# Sheet_1_2024-01-18.net
KiCad netlist of a schematic drawn in Altium Designer
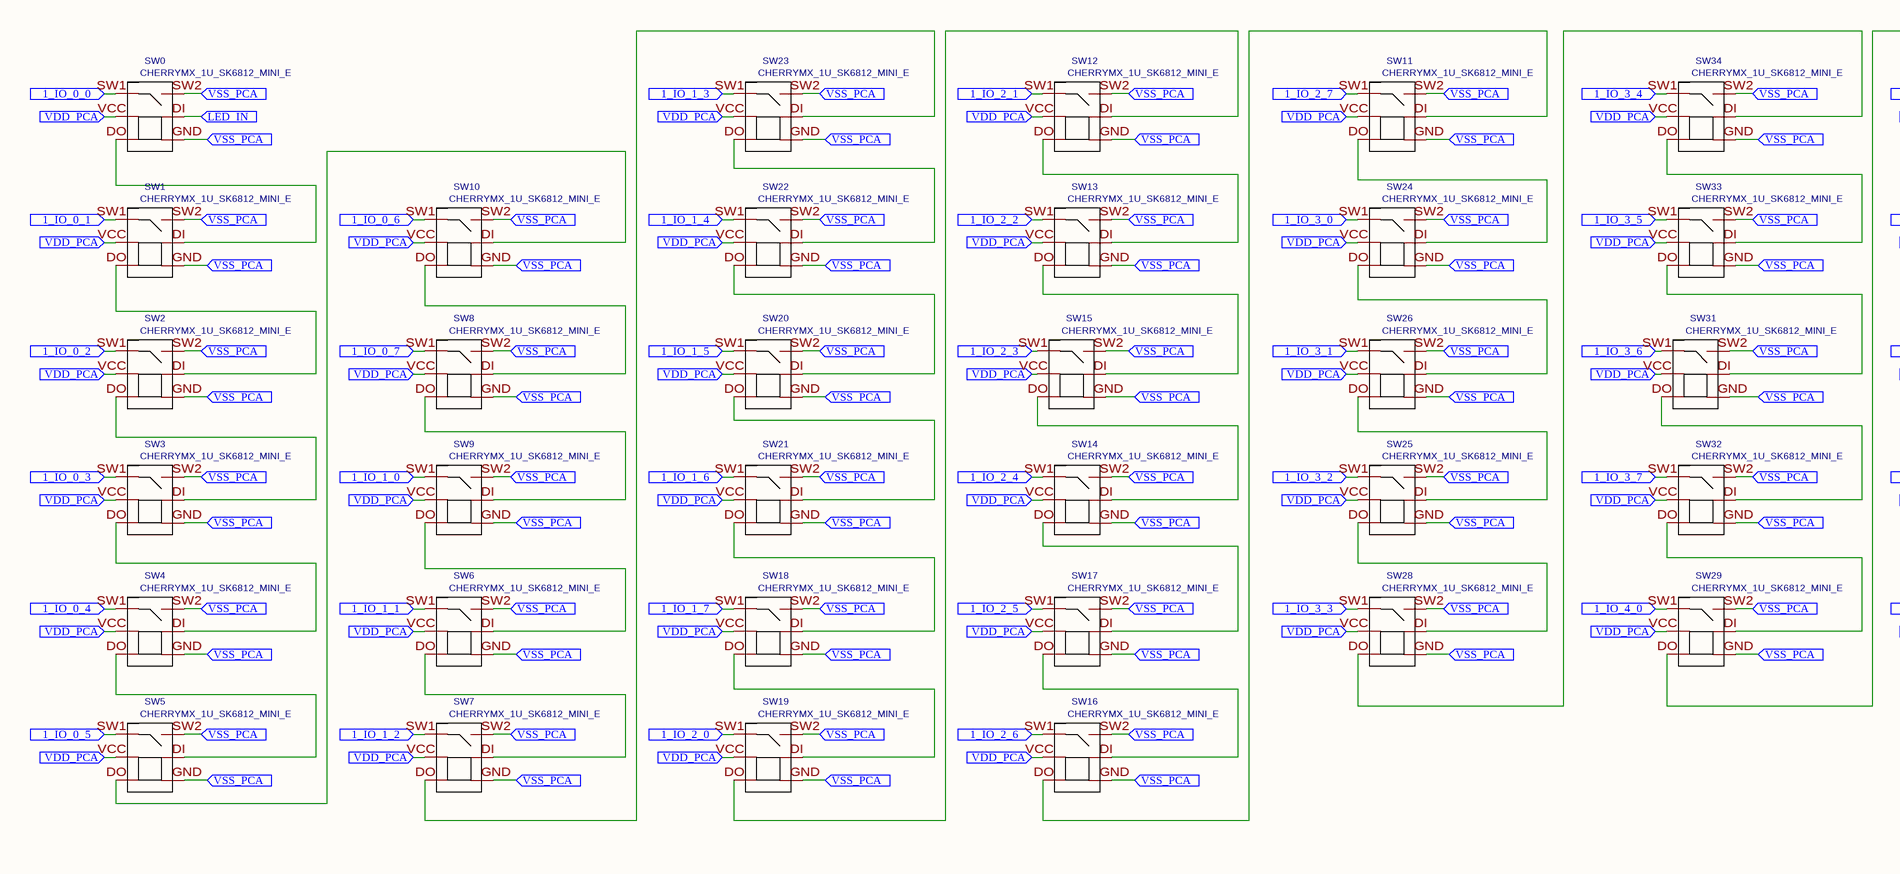
[diagram p0: Sheet_1_2024-01-18.schdoc, top left]
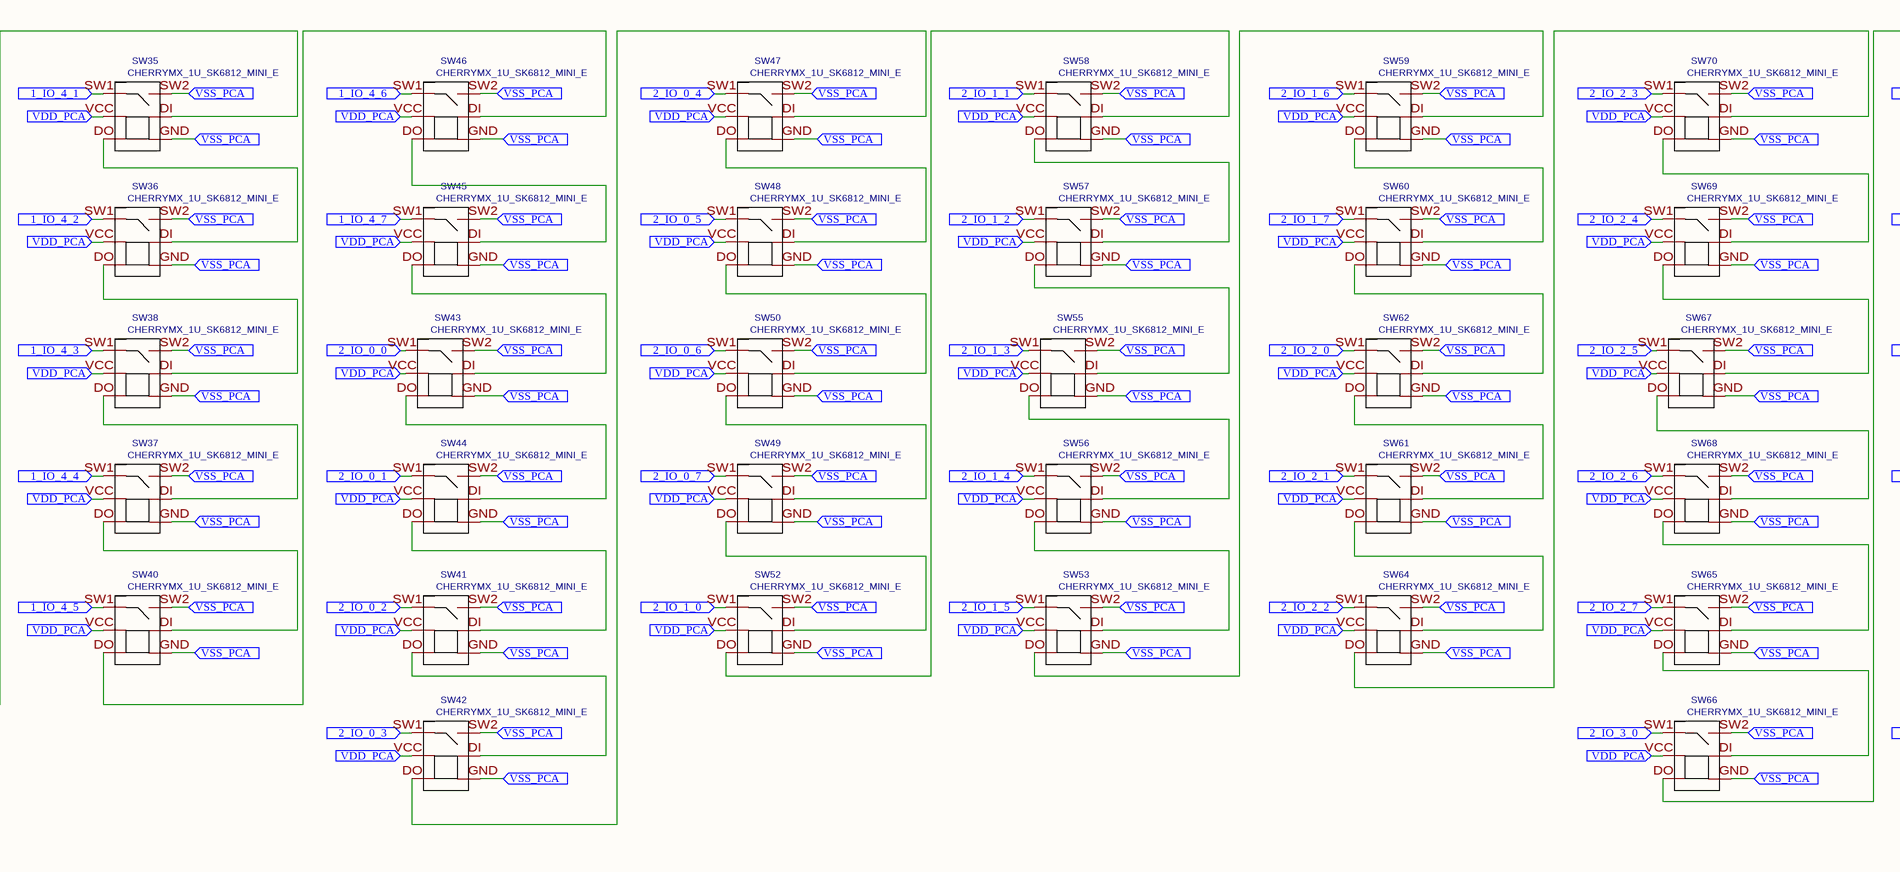
[diagram p1: Sheet_1_2024-01-18.schdoc, top middle]
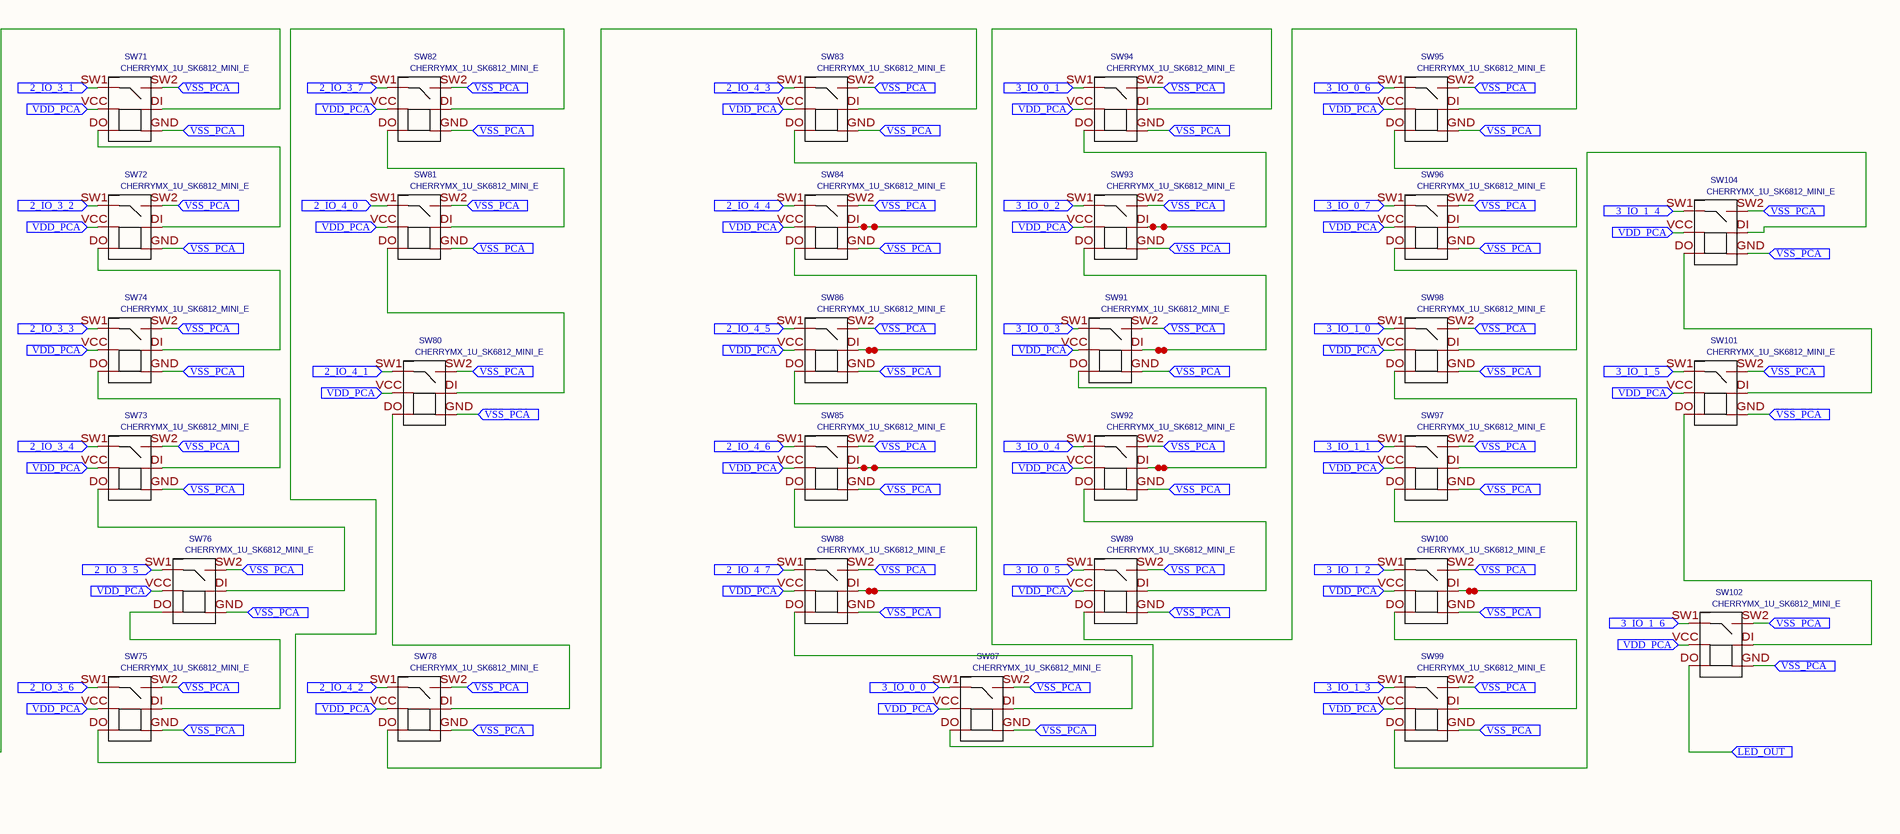
[diagram p2: Sheet_1_2024-01-18.schdoc, top right]
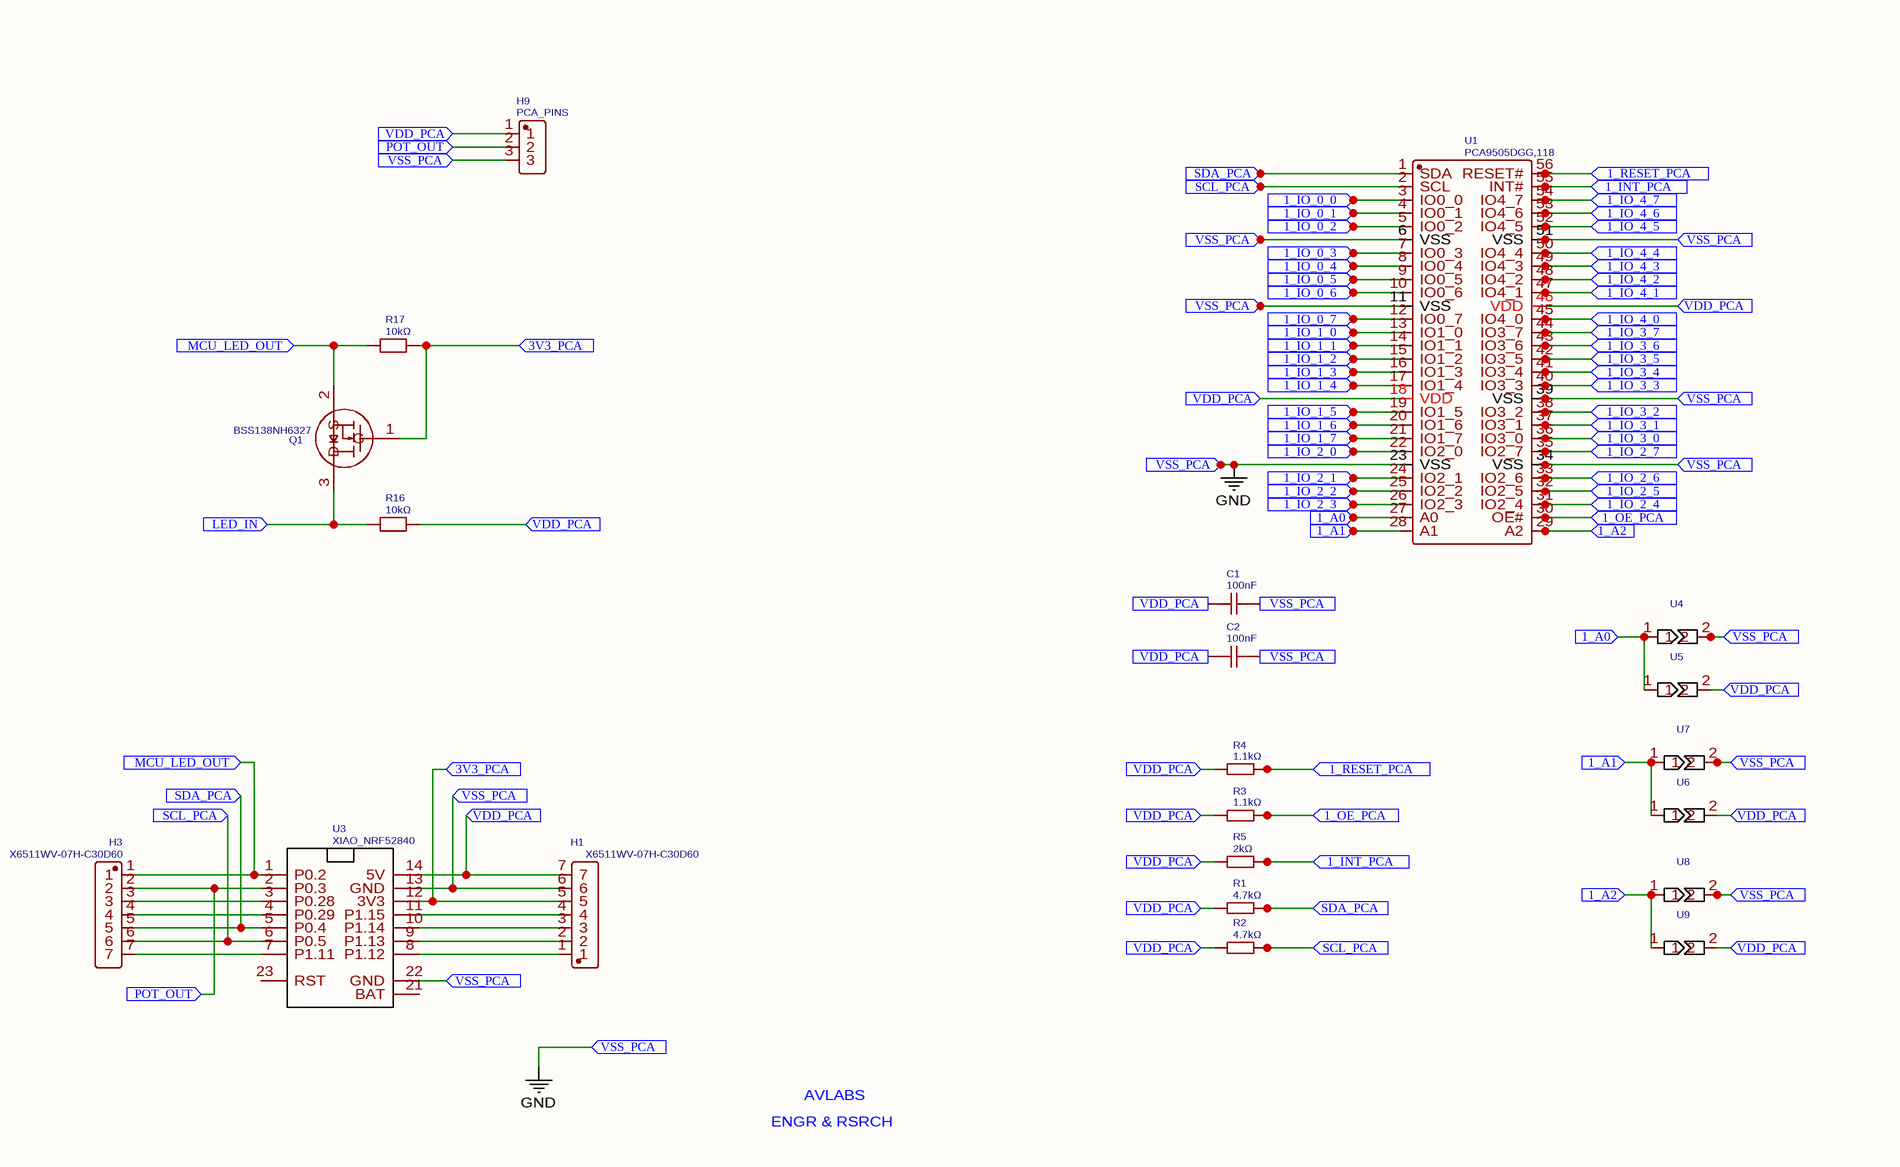
[diagram p3: Sheet_1_2024-01-18.schdoc, bottom left]
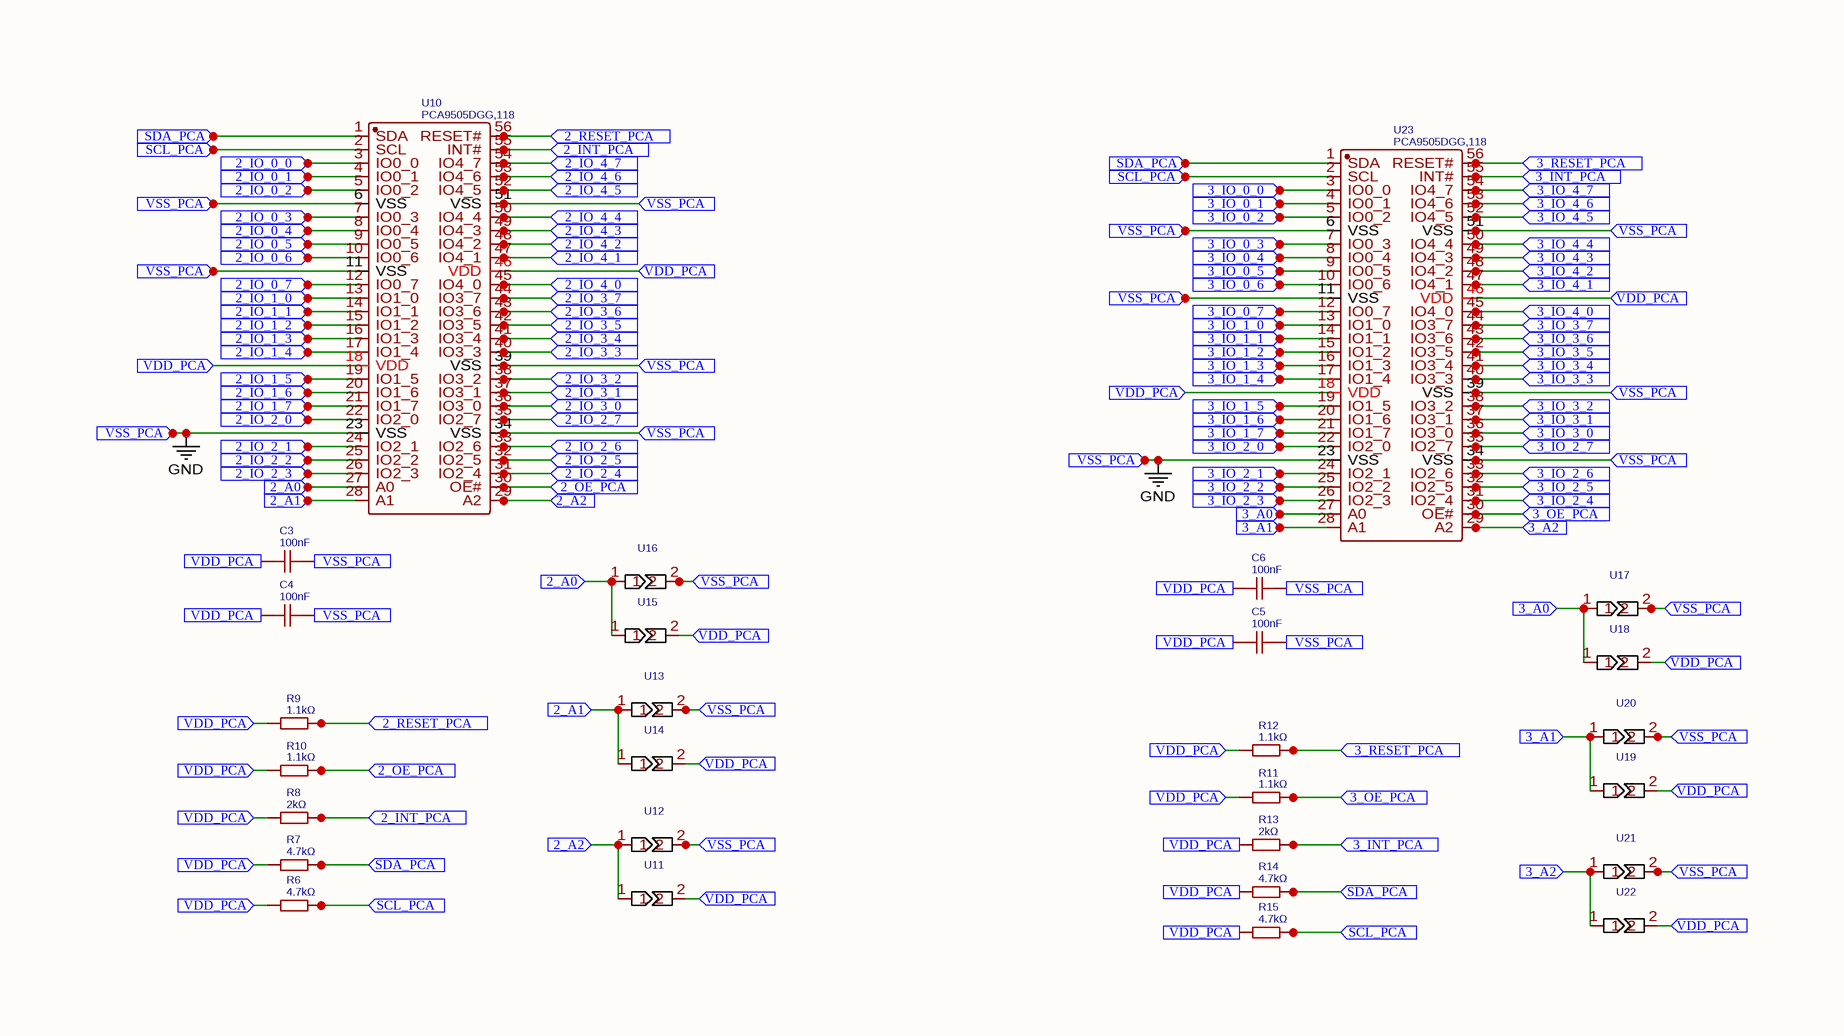
[diagram p4: Sheet_1_2024-01-18.schdoc, bottom middle]

(export (version "E")
  (design (tool "Eeschema 10.0.6"))
  (components
    (comp (ref "C1")
      (value "100nF")
      (fields
        (field (name "MANUFACTURER") "muRata(村田)")
        (field (name "MANUFACTURER PART") "GRM21BR71H104KA01L")
      )
      (libsource (lib "altium-import") (part "root_0_100nF_"))
    )
    (comp (ref "C2")
      (value "100nF")
      (fields
        (field (name "MANUFACTURER") "muRata(村田)")
        (field (name "MANUFACTURER PART") "GRM21BR71H104KA01L")
      )
      (libsource (lib "altium-import") (part "root_0_100nF_"))
    )
    (comp (ref "C3")
      (value "100nF")
      (fields
        (field (name "MANUFACTURER") "muRata(村田)")
        (field (name "MANUFACTURER PART") "GRM21BR71H104KA01L")
      )
      (libsource (lib "altium-import") (part "root_0_100nF_"))
    )
    (comp (ref "C4")
      (value "100nF")
      (fields
        (field (name "MANUFACTURER") "muRata(村田)")
        (field (name "MANUFACTURER PART") "GRM21BR71H104KA01L")
      )
      (libsource (lib "altium-import") (part "root_0_100nF_"))
    )
    (comp (ref "C5")
      (value "100nF")
      (fields
        (field (name "MANUFACTURER") "muRata(村田)")
        (field (name "MANUFACTURER PART") "GRM21BR71H104KA01L")
      )
      (libsource (lib "altium-import") (part "root_0_100nF_"))
    )
    (comp (ref "C6")
      (value "100nF")
      (fields
        (field (name "MANUFACTURER") "muRata(村田)")
        (field (name "MANUFACTURER PART") "GRM21BR71H104KA01L")
      )
      (libsource (lib "altium-import") (part "root_0_100nF_"))
    )
    (comp (ref "H1")
      (value "X6511WV-07H-C30D60")
      (fields (field (name "MANUFACTURER") "XKB Connectivity(中国星坤)") (field (name "CONTRIBUTOR") "LCSC"))
      (libsource (lib "altium-import") (part "root_2_X6511WV-07H-C30D60_"))
    )
    (comp (ref "H3")
      (value "X6511WV-07H-C30D60")
      (fields (field (name "MANUFACTURER") "XKB Connectivity(中国星坤)") (field (name "CONTRIBUTOR") "LCSC"))
      (libsource (lib "altium-import") (part "root_0_X6511WV-07H-C30D60_"))
    )
    (comp (ref "H9")
      (value "PCA_PINS")
      (fields
        (field (name "MANUFACTURER") "XKB Connectivity(中国星坤)")
        (field (name "MANUFACTURER PART") "X6511WV-03H-C30D60")
        (field (name "CONTRIBUTOR") "LCSC")
      )
      (libsource (lib "altium-import") (part "root_0_PCA_PINS_"))
    )
    (comp (ref "Q1")
      (value "BSS138NH6327")
      (fields (field (name "MANUFACTURER") "Infineon(英飞凌)") (field (name "CONTRIBUTOR") "LCSC"))
      (libsource (lib "altium-import") (part "root_0_BSS138NH6327_"))
    )
    (comp (ref "R1")
      (value "4.7kΩ")
      (fields
        (field (name "MANUFACTURER") "KOA")
        (field (name "MANUFACTURER PART") "RN732ATTD4701B25")
        (field (name "CONTRIBUTOR") "LCSC")
      )
      (libsource (lib "altium-import") (part "root_0_4.7kΩ_"))
    )
    (comp (ref "R2")
      (value "4.7kΩ")
      (fields
        (field (name "MANUFACTURER") "KOA")
        (field (name "MANUFACTURER PART") "RN732ATTD4701B25")
        (field (name "CONTRIBUTOR") "LCSC")
      )
      (libsource (lib "altium-import") (part "root_0_4.7kΩ_"))
    )
    (comp (ref "R3")
      (value "1.1kΩ")
      (fields
        (field (name "MANUFACTURER") "KOA")
        (field (name "MANUFACTURER PART") "RN732ATTD1101B25")
        (field (name "CONTRIBUTOR") "LCSC")
      )
      (libsource (lib "altium-import") (part "root_0_1.1kΩ_"))
    )
    (comp (ref "R4")
      (value "1.1kΩ")
      (fields
        (field (name "MANUFACTURER") "KOA")
        (field (name "MANUFACTURER PART") "RN732ATTD1101B25")
        (field (name "CONTRIBUTOR") "LCSC")
      )
      (libsource (lib "altium-import") (part "root_0_1.1kΩ_"))
    )
    (comp (ref "R5")
      (value "2kΩ")
      (fields
        (field (name "MANUFACTURER") "KOA")
        (field (name "MANUFACTURER PART") "RN732ATTD2001B25")
        (field (name "CONTRIBUTOR") "LCSC")
      )
      (libsource (lib "altium-import") (part "root_0_2kΩ_"))
    )
    (comp (ref "R6")
      (value "4.7kΩ")
      (fields
        (field (name "MANUFACTURER") "KOA")
        (field (name "MANUFACTURER PART") "RN732ATTD4701B25")
        (field (name "CONTRIBUTOR") "LCSC")
      )
      (libsource (lib "altium-import") (part "root_0_4.7kΩ_"))
    )
    (comp (ref "R7")
      (value "4.7kΩ")
      (fields
        (field (name "MANUFACTURER") "KOA")
        (field (name "MANUFACTURER PART") "RN732ATTD4701B25")
        (field (name "CONTRIBUTOR") "LCSC")
      )
      (libsource (lib "altium-import") (part "root_0_4.7kΩ_"))
    )
    (comp (ref "R8")
      (value "2kΩ")
      (fields
        (field (name "MANUFACTURER") "KOA")
        (field (name "MANUFACTURER PART") "RN732ATTD2001B25")
        (field (name "CONTRIBUTOR") "LCSC")
      )
      (libsource (lib "altium-import") (part "root_0_2kΩ_"))
    )
    (comp (ref "R9")
      (value "1.1kΩ")
      (fields
        (field (name "MANUFACTURER") "KOA")
        (field (name "MANUFACTURER PART") "RN732ATTD1101B25")
        (field (name "CONTRIBUTOR") "LCSC")
      )
      (libsource (lib "altium-import") (part "root_0_1.1kΩ_"))
    )
    (comp (ref "R10")
      (value "1.1kΩ")
      (fields
        (field (name "MANUFACTURER") "KOA")
        (field (name "MANUFACTURER PART") "RN732ATTD1101B25")
        (field (name "CONTRIBUTOR") "LCSC")
      )
      (libsource (lib "altium-import") (part "root_0_1.1kΩ_"))
    )
    (comp (ref "R11")
      (value "1.1kΩ")
      (fields
        (field (name "MANUFACTURER") "KOA")
        (field (name "MANUFACTURER PART") "RN732ATTD1101B25")
        (field (name "CONTRIBUTOR") "LCSC")
      )
      (libsource (lib "altium-import") (part "root_0_1.1kΩ_"))
    )
    (comp (ref "R12")
      (value "1.1kΩ")
      (fields
        (field (name "MANUFACTURER") "KOA")
        (field (name "MANUFACTURER PART") "RN732ATTD1101B25")
        (field (name "CONTRIBUTOR") "LCSC")
      )
      (libsource (lib "altium-import") (part "root_0_1.1kΩ_"))
    )
    (comp (ref "R13")
      (value "2kΩ")
      (fields
        (field (name "MANUFACTURER") "KOA")
        (field (name "MANUFACTURER PART") "RN732ATTD2001B25")
        (field (name "CONTRIBUTOR") "LCSC")
      )
      (libsource (lib "altium-import") (part "root_0_2kΩ_"))
    )
    (comp (ref "R14")
      (value "4.7kΩ")
      (fields
        (field (name "MANUFACTURER") "KOA")
        (field (name "MANUFACTURER PART") "RN732ATTD4701B25")
        (field (name "CONTRIBUTOR") "LCSC")
      )
      (libsource (lib "altium-import") (part "root_0_4.7kΩ_"))
    )
    (comp (ref "R15")
      (value "4.7kΩ")
      (fields
        (field (name "MANUFACTURER") "KOA")
        (field (name "MANUFACTURER PART") "RN732ATTD4701B25")
        (field (name "CONTRIBUTOR") "LCSC")
      )
      (libsource (lib "altium-import") (part "root_0_4.7kΩ_"))
    )
    (comp (ref "R16")
      (value "10kΩ")
      (fields
        (field (name "MANUFACTURER") "KOA")
        (field (name "MANUFACTURER PART") "RN732ATTD1002B10")
        (field (name "CONTRIBUTOR") "LCSC")
      )
      (libsource (lib "altium-import") (part "root_0_10kΩ_"))
    )
    (comp (ref "R17")
      (value "10kΩ")
      (fields
        (field (name "MANUFACTURER") "KOA")
        (field (name "MANUFACTURER PART") "RN732ATTD1002B10")
        (field (name "CONTRIBUTOR") "LCSC")
      )
      (libsource (lib "altium-import") (part "root_0_10kΩ_"))
    )
    (comp (ref "SW0")
      (value "CHERRYMX_1U_SK6812_MINI_E")
      (fields (field (name "CONTRIBUTOR") "Andrea Peron"))
      (libsource (lib "altium-import") (part "root_0_CHERRYMX_1U_SK6812_MINI_E_"))
    )
    (comp (ref "SW1")
      (value "CHERRYMX_1U_SK6812_MINI_E")
      (fields (field (name "CONTRIBUTOR") "Andrea Peron"))
      (libsource (lib "altium-import") (part "root_0_CHERRYMX_1U_SK6812_MINI_E_"))
    )
    (comp (ref "SW2")
      (value "CHERRYMX_1U_SK6812_MINI_E")
      (fields (field (name "CONTRIBUTOR") "Andrea Peron"))
      (libsource (lib "altium-import") (part "root_0_CHERRYMX_1U_SK6812_MINI_E_"))
    )
    (comp (ref "SW3")
      (value "CHERRYMX_1U_SK6812_MINI_E")
      (fields (field (name "CONTRIBUTOR") "Andrea Peron"))
      (libsource (lib "altium-import") (part "root_0_CHERRYMX_1U_SK6812_MINI_E_"))
    )
    (comp (ref "SW4")
      (value "CHERRYMX_1U_SK6812_MINI_E")
      (fields (field (name "CONTRIBUTOR") "Andrea Peron"))
      (libsource (lib "altium-import") (part "root_0_CHERRYMX_1U_SK6812_MINI_E_"))
    )
    (comp (ref "SW5")
      (value "CHERRYMX_1U_SK6812_MINI_E")
      (fields (field (name "CONTRIBUTOR") "Andrea Peron"))
      (libsource (lib "altium-import") (part "root_0_CHERRYMX_1U_SK6812_MINI_E_"))
    )
    (comp (ref "SW6")
      (value "CHERRYMX_1U_SK6812_MINI_E")
      (fields (field (name "CONTRIBUTOR") "Andrea Peron"))
      (libsource (lib "altium-import") (part "root_0_CHERRYMX_1U_SK6812_MINI_E_"))
    )
    (comp (ref "SW7")
      (value "CHERRYMX_1U_SK6812_MINI_E")
      (fields (field (name "CONTRIBUTOR") "Andrea Peron"))
      (libsource (lib "altium-import") (part "root_0_CHERRYMX_1U_SK6812_MINI_E_"))
    )
    (comp (ref "SW8")
      (value "CHERRYMX_1U_SK6812_MINI_E")
      (fields (field (name "CONTRIBUTOR") "Andrea Peron"))
      (libsource (lib "altium-import") (part "root_0_CHERRYMX_1U_SK6812_MINI_E_"))
    )
    (comp (ref "SW9")
      (value "CHERRYMX_1U_SK6812_MINI_E")
      (fields (field (name "CONTRIBUTOR") "Andrea Peron"))
      (libsource (lib "altium-import") (part "root_0_CHERRYMX_1U_SK6812_MINI_E_"))
    )
    (comp (ref "SW10")
      (value "CHERRYMX_1U_SK6812_MINI_E")
      (fields (field (name "CONTRIBUTOR") "Andrea Peron"))
      (libsource (lib "altium-import") (part "root_0_CHERRYMX_1U_SK6812_MINI_E_"))
    )
    (comp (ref "SW11")
      (value "CHERRYMX_1U_SK6812_MINI_E")
      (fields (field (name "CONTRIBUTOR") "Andrea Peron"))
      (libsource (lib "altium-import") (part "root_0_CHERRYMX_1U_SK6812_MINI_E_"))
    )
    (comp (ref "SW12")
      (value "CHERRYMX_1U_SK6812_MINI_E")
      (fields (field (name "CONTRIBUTOR") "Andrea Peron"))
      (libsource (lib "altium-import") (part "root_0_CHERRYMX_1U_SK6812_MINI_E_"))
    )
    (comp (ref "SW13")
      (value "CHERRYMX_1U_SK6812_MINI_E")
      (fields (field (name "CONTRIBUTOR") "Andrea Peron"))
      (libsource (lib "altium-import") (part "root_0_CHERRYMX_1U_SK6812_MINI_E_"))
    )
    (comp (ref "SW14")
      (value "CHERRYMX_1U_SK6812_MINI_E")
      (fields (field (name "CONTRIBUTOR") "Andrea Peron"))
      (libsource (lib "altium-import") (part "root_0_CHERRYMX_1U_SK6812_MINI_E_"))
    )
    (comp (ref "SW15")
      (value "CHERRYMX_1U_SK6812_MINI_E")
      (fields (field (name "CONTRIBUTOR") "Andrea Peron"))
      (libsource (lib "altium-import") (part "root_0_CHERRYMX_1U_SK6812_MINI_E_"))
    )
    (comp (ref "SW16")
      (value "CHERRYMX_1U_SK6812_MINI_E")
      (fields (field (name "CONTRIBUTOR") "Andrea Peron"))
      (libsource (lib "altium-import") (part "root_0_CHERRYMX_1U_SK6812_MINI_E_"))
    )
    (comp (ref "SW17")
      (value "CHERRYMX_1U_SK6812_MINI_E")
      (fields (field (name "CONTRIBUTOR") "Andrea Peron"))
      (libsource (lib "altium-import") (part "root_0_CHERRYMX_1U_SK6812_MINI_E_"))
    )
    (comp (ref "SW18")
      (value "CHERRYMX_1U_SK6812_MINI_E")
      (fields (field (name "CONTRIBUTOR") "Andrea Peron"))
      (libsource (lib "altium-import") (part "root_0_CHERRYMX_1U_SK6812_MINI_E_"))
    )
    (comp (ref "SW19")
      (value "CHERRYMX_1U_SK6812_MINI_E")
      (fields (field (name "CONTRIBUTOR") "Andrea Peron"))
      (libsource (lib "altium-import") (part "root_0_CHERRYMX_1U_SK6812_MINI_E_"))
    )
    (comp (ref "SW20")
      (value "CHERRYMX_1U_SK6812_MINI_E")
      (fields (field (name "CONTRIBUTOR") "Andrea Peron"))
      (libsource (lib "altium-import") (part "root_0_CHERRYMX_1U_SK6812_MINI_E_"))
    )
    (comp (ref "SW21")
      (value "CHERRYMX_1U_SK6812_MINI_E")
      (fields (field (name "CONTRIBUTOR") "Andrea Peron"))
      (libsource (lib "altium-import") (part "root_0_CHERRYMX_1U_SK6812_MINI_E_"))
    )
    (comp (ref "SW22")
      (value "CHERRYMX_1U_SK6812_MINI_E")
      (fields (field (name "CONTRIBUTOR") "Andrea Peron"))
      (libsource (lib "altium-import") (part "root_0_CHERRYMX_1U_SK6812_MINI_E_"))
    )
    (comp (ref "SW23")
      (value "CHERRYMX_1U_SK6812_MINI_E")
      (fields (field (name "CONTRIBUTOR") "Andrea Peron"))
      (libsource (lib "altium-import") (part "root_0_CHERRYMX_1U_SK6812_MINI_E_"))
    )
    (comp (ref "SW24")
      (value "CHERRYMX_1U_SK6812_MINI_E")
      (fields (field (name "CONTRIBUTOR") "Andrea Peron"))
      (libsource (lib "altium-import") (part "root_0_CHERRYMX_1U_SK6812_MINI_E_"))
    )
    (comp (ref "SW25")
      (value "CHERRYMX_1U_SK6812_MINI_E")
      (fields (field (name "CONTRIBUTOR") "Andrea Peron"))
      (libsource (lib "altium-import") (part "root_0_CHERRYMX_1U_SK6812_MINI_E_"))
    )
    (comp (ref "SW26")
      (value "CHERRYMX_1U_SK6812_MINI_E")
      (fields (field (name "CONTRIBUTOR") "Andrea Peron"))
      (libsource (lib "altium-import") (part "root_0_CHERRYMX_1U_SK6812_MINI_E_"))
    )
    (comp (ref "SW28")
      (value "CHERRYMX_1U_SK6812_MINI_E")
      (fields (field (name "CONTRIBUTOR") "Andrea Peron"))
      (libsource (lib "altium-import") (part "root_0_CHERRYMX_1U_SK6812_MINI_E_"))
    )
    (comp (ref "SW29")
      (value "CHERRYMX_1U_SK6812_MINI_E")
      (fields (field (name "CONTRIBUTOR") "Andrea Peron"))
      (libsource (lib "altium-import") (part "root_0_CHERRYMX_1U_SK6812_MINI_E_"))
    )
    (comp (ref "SW31")
      (value "CHERRYMX_1U_SK6812_MINI_E")
      (fields (field (name "CONTRIBUTOR") "Andrea Peron"))
      (libsource (lib "altium-import") (part "root_0_CHERRYMX_1U_SK6812_MINI_E_"))
    )
    (comp (ref "SW32")
      (value "CHERRYMX_1U_SK6812_MINI_E")
      (fields (field (name "CONTRIBUTOR") "Andrea Peron"))
      (libsource (lib "altium-import") (part "root_0_CHERRYMX_1U_SK6812_MINI_E_"))
    )
    (comp (ref "SW33")
      (value "CHERRYMX_1U_SK6812_MINI_E")
      (fields (field (name "CONTRIBUTOR") "Andrea Peron"))
      (libsource (lib "altium-import") (part "root_0_CHERRYMX_1U_SK6812_MINI_E_"))
    )
    (comp (ref "SW34")
      (value "CHERRYMX_1U_SK6812_MINI_E")
      (fields (field (name "CONTRIBUTOR") "Andrea Peron"))
      (libsource (lib "altium-import") (part "root_0_CHERRYMX_1U_SK6812_MINI_E_"))
    )
    (comp (ref "SW35")
      (value "CHERRYMX_1U_SK6812_MINI_E")
      (fields (field (name "CONTRIBUTOR") "Andrea Peron"))
      (libsource (lib "altium-import") (part "root_0_CHERRYMX_1U_SK6812_MINI_E_"))
    )
    (comp (ref "SW36")
      (value "CHERRYMX_1U_SK6812_MINI_E")
      (fields (field (name "CONTRIBUTOR") "Andrea Peron"))
      (libsource (lib "altium-import") (part "root_0_CHERRYMX_1U_SK6812_MINI_E_"))
    )
    (comp (ref "SW37")
      (value "CHERRYMX_1U_SK6812_MINI_E")
      (fields (field (name "CONTRIBUTOR") "Andrea Peron"))
      (libsource (lib "altium-import") (part "root_0_CHERRYMX_1U_SK6812_MINI_E_"))
    )
    (comp (ref "SW38")
      (value "CHERRYMX_1U_SK6812_MINI_E")
      (fields (field (name "CONTRIBUTOR") "Andrea Peron"))
      (libsource (lib "altium-import") (part "root_0_CHERRYMX_1U_SK6812_MINI_E_"))
    )
    (comp (ref "SW40")
      (value "CHERRYMX_1U_SK6812_MINI_E")
      (fields (field (name "CONTRIBUTOR") "Andrea Peron"))
      (libsource (lib "altium-import") (part "root_0_CHERRYMX_1U_SK6812_MINI_E_"))
    )
    (comp (ref "SW41")
      (value "CHERRYMX_1U_SK6812_MINI_E")
      (fields (field (name "CONTRIBUTOR") "Andrea Peron"))
      (libsource (lib "altium-import") (part "root_0_CHERRYMX_1U_SK6812_MINI_E_"))
    )
    (comp (ref "SW42")
      (value "CHERRYMX_1U_SK6812_MINI_E")
      (fields (field (name "CONTRIBUTOR") "Andrea Peron"))
      (libsource (lib "altium-import") (part "root_0_CHERRYMX_1U_SK6812_MINI_E_"))
    )
    (comp (ref "SW43")
      (value "CHERRYMX_1U_SK6812_MINI_E")
      (fields (field (name "CONTRIBUTOR") "Andrea Peron"))
      (libsource (lib "altium-import") (part "root_0_CHERRYMX_1U_SK6812_MINI_E_"))
    )
    (comp (ref "SW44")
      (value "CHERRYMX_1U_SK6812_MINI_E")
      (fields (field (name "CONTRIBUTOR") "Andrea Peron"))
      (libsource (lib "altium-import") (part "root_0_CHERRYMX_1U_SK6812_MINI_E_"))
    )
    (comp (ref "SW45")
      (value "CHERRYMX_1U_SK6812_MINI_E")
      (fields (field (name "CONTRIBUTOR") "Andrea Peron"))
      (libsource (lib "altium-import") (part "root_0_CHERRYMX_1U_SK6812_MINI_E_"))
    )
    (comp (ref "SW46")
      (value "CHERRYMX_1U_SK6812_MINI_E")
      (fields (field (name "CONTRIBUTOR") "Andrea Peron"))
      (libsource (lib "altium-import") (part "root_0_CHERRYMX_1U_SK6812_MINI_E_"))
    )
    (comp (ref "SW47")
      (value "CHERRYMX_1U_SK6812_MINI_E")
      (fields (field (name "CONTRIBUTOR") "Andrea Peron"))
      (libsource (lib "altium-import") (part "root_0_CHERRYMX_1U_SK6812_MINI_E_"))
    )
    (comp (ref "SW48")
      (value "CHERRYMX_1U_SK6812_MINI_E")
      (fields (field (name "CONTRIBUTOR") "Andrea Peron"))
      (libsource (lib "altium-import") (part "root_0_CHERRYMX_1U_SK6812_MINI_E_"))
    )
    (comp (ref "SW49")
      (value "CHERRYMX_1U_SK6812_MINI_E")
      (fields (field (name "CONTRIBUTOR") "Andrea Peron"))
      (libsource (lib "altium-import") (part "root_0_CHERRYMX_1U_SK6812_MINI_E_"))
    )
    (comp (ref "SW50")
      (value "CHERRYMX_1U_SK6812_MINI_E")
      (fields (field (name "CONTRIBUTOR") "Andrea Peron"))
      (libsource (lib "altium-import") (part "root_0_CHERRYMX_1U_SK6812_MINI_E_"))
    )
    (comp (ref "SW52")
      (value "CHERRYMX_1U_SK6812_MINI_E")
      (fields (field (name "CONTRIBUTOR") "Andrea Peron"))
      (libsource (lib "altium-import") (part "root_0_CHERRYMX_1U_SK6812_MINI_E_"))
    )
    (comp (ref "SW53")
      (value "CHERRYMX_1U_SK6812_MINI_E")
      (fields (field (name "CONTRIBUTOR") "Andrea Peron"))
      (libsource (lib "altium-import") (part "root_0_CHERRYMX_1U_SK6812_MINI_E_"))
    )
    (comp (ref "SW55")
      (value "CHERRYMX_1U_SK6812_MINI_E")
      (fields (field (name "CONTRIBUTOR") "Andrea Peron"))
      (libsource (lib "altium-import") (part "root_0_CHERRYMX_1U_SK6812_MINI_E_"))
    )
    (comp (ref "SW56")
      (value "CHERRYMX_1U_SK6812_MINI_E")
      (fields (field (name "CONTRIBUTOR") "Andrea Peron"))
      (libsource (lib "altium-import") (part "root_0_CHERRYMX_1U_SK6812_MINI_E_"))
    )
    (comp (ref "SW57")
      (value "CHERRYMX_1U_SK6812_MINI_E")
      (fields (field (name "CONTRIBUTOR") "Andrea Peron"))
      (libsource (lib "altium-import") (part "root_0_CHERRYMX_1U_SK6812_MINI_E_"))
    )
    (comp (ref "SW58")
      (value "CHERRYMX_1U_SK6812_MINI_E")
      (fields (field (name "CONTRIBUTOR") "Andrea Peron"))
      (libsource (lib "altium-import") (part "root_0_CHERRYMX_1U_SK6812_MINI_E_"))
    )
    (comp (ref "SW59")
      (value "CHERRYMX_1U_SK6812_MINI_E")
      (fields (field (name "CONTRIBUTOR") "Andrea Peron"))
      (libsource (lib "altium-import") (part "root_0_CHERRYMX_1U_SK6812_MINI_E_"))
    )
    (comp (ref "SW60")
      (value "CHERRYMX_1U_SK6812_MINI_E")
      (fields (field (name "CONTRIBUTOR") "Andrea Peron"))
      (libsource (lib "altium-import") (part "root_0_CHERRYMX_1U_SK6812_MINI_E_"))
    )
    (comp (ref "SW61")
      (value "CHERRYMX_1U_SK6812_MINI_E")
      (fields (field (name "CONTRIBUTOR") "Andrea Peron"))
      (libsource (lib "altium-import") (part "root_0_CHERRYMX_1U_SK6812_MINI_E_"))
    )
    (comp (ref "SW62")
      (value "CHERRYMX_1U_SK6812_MINI_E")
      (fields (field (name "CONTRIBUTOR") "Andrea Peron"))
      (libsource (lib "altium-import") (part "root_0_CHERRYMX_1U_SK6812_MINI_E_"))
    )
    (comp (ref "SW64")
      (value "CHERRYMX_1U_SK6812_MINI_E")
      (fields (field (name "CONTRIBUTOR") "Andrea Peron"))
      (libsource (lib "altium-import") (part "root_0_CHERRYMX_1U_SK6812_MINI_E_"))
    )
    (comp (ref "SW65")
      (value "CHERRYMX_1U_SK6812_MINI_E")
      (fields (field (name "CONTRIBUTOR") "Andrea Peron"))
      (libsource (lib "altium-import") (part "root_0_CHERRYMX_1U_SK6812_MINI_E_"))
    )
    (comp (ref "SW66")
      (value "CHERRYMX_1U_SK6812_MINI_E")
      (fields (field (name "CONTRIBUTOR") "Andrea Peron"))
      (libsource (lib "altium-import") (part "root_0_CHERRYMX_1U_SK6812_MINI_E_"))
    )
    (comp (ref "SW67")
      (value "CHERRYMX_1U_SK6812_MINI_E")
      (fields (field (name "CONTRIBUTOR") "Andrea Peron"))
      (libsource (lib "altium-import") (part "root_0_CHERRYMX_1U_SK6812_MINI_E_"))
    )
    (comp (ref "SW68")
      (value "CHERRYMX_1U_SK6812_MINI_E")
      (fields (field (name "CONTRIBUTOR") "Andrea Peron"))
      (libsource (lib "altium-import") (part "root_0_CHERRYMX_1U_SK6812_MINI_E_"))
    )
    (comp (ref "SW69")
      (value "CHERRYMX_1U_SK6812_MINI_E")
      (fields (field (name "CONTRIBUTOR") "Andrea Peron"))
      (libsource (lib "altium-import") (part "root_0_CHERRYMX_1U_SK6812_MINI_E_"))
    )
    (comp (ref "SW70")
      (value "CHERRYMX_1U_SK6812_MINI_E")
      (fields (field (name "CONTRIBUTOR") "Andrea Peron"))
      (libsource (lib "altium-import") (part "root_0_CHERRYMX_1U_SK6812_MINI_E_"))
    )
    (comp (ref "SW71")
      (value "CHERRYMX_1U_SK6812_MINI_E")
      (fields (field (name "CONTRIBUTOR") "Andrea Peron"))
      (libsource (lib "altium-import") (part "root_0_CHERRYMX_1U_SK6812_MINI_E_"))
    )
    (comp (ref "SW72")
      (value "CHERRYMX_1U_SK6812_MINI_E")
      (fields (field (name "CONTRIBUTOR") "Andrea Peron"))
      (libsource (lib "altium-import") (part "root_0_CHERRYMX_1U_SK6812_MINI_E_"))
    )
    (comp (ref "SW73")
      (value "CHERRYMX_1U_SK6812_MINI_E")
      (fields (field (name "CONTRIBUTOR") "Andrea Peron"))
      (libsource (lib "altium-import") (part "root_0_CHERRYMX_1U_SK6812_MINI_E_"))
    )
    (comp (ref "SW74")
      (value "CHERRYMX_1U_SK6812_MINI_E")
      (fields (field (name "CONTRIBUTOR") "Andrea Peron"))
      (libsource (lib "altium-import") (part "root_0_CHERRYMX_1U_SK6812_MINI_E_"))
    )
    (comp (ref "SW75")
      (value "CHERRYMX_1U_SK6812_MINI_E")
      (fields (field (name "CONTRIBUTOR") "Andrea Peron"))
      (libsource (lib "altium-import") (part "root_0_CHERRYMX_1U_SK6812_MINI_E_"))
    )
    (comp (ref "SW76")
      (value "CHERRYMX_1U_SK6812_MINI_E")
      (fields (field (name "CONTRIBUTOR") "Andrea Peron"))
      (libsource (lib "altium-import") (part "root_0_CHERRYMX_1U_SK6812_MINI_E_"))
    )
    (comp (ref "SW78")
      (value "CHERRYMX_1U_SK6812_MINI_E")
      (fields (field (name "CONTRIBUTOR") "Andrea Peron"))
      (libsource (lib "altium-import") (part "root_0_CHERRYMX_1U_SK6812_MINI_E_"))
    )
    (comp (ref "SW80")
      (value "CHERRYMX_1U_SK6812_MINI_E")
      (fields (field (name "CONTRIBUTOR") "Andrea Peron"))
      (libsource (lib "altium-import") (part "root_0_CHERRYMX_1U_SK6812_MINI_E_"))
    )
    (comp (ref "SW81")
      (value "CHERRYMX_1U_SK6812_MINI_E")
      (fields (field (name "CONTRIBUTOR") "Andrea Peron"))
      (libsource (lib "altium-import") (part "root_0_CHERRYMX_1U_SK6812_MINI_E_"))
    )
    (comp (ref "SW82")
      (value "CHERRYMX_1U_SK6812_MINI_E")
      (fields (field (name "CONTRIBUTOR") "Andrea Peron"))
      (libsource (lib "altium-import") (part "root_0_CHERRYMX_1U_SK6812_MINI_E_"))
    )
    (comp (ref "SW83")
      (value "CHERRYMX_1U_SK6812_MINI_E")
      (fields (field (name "CONTRIBUTOR") "Andrea Peron"))
      (libsource (lib "altium-import") (part "root_0_CHERRYMX_1U_SK6812_MINI_E_"))
    )
    (comp (ref "SW84")
      (value "CHERRYMX_1U_SK6812_MINI_E")
      (fields (field (name "CONTRIBUTOR") "Andrea Peron"))
      (libsource (lib "altium-import") (part "root_0_CHERRYMX_1U_SK6812_MINI_E_"))
    )
    (comp (ref "SW85")
      (value "CHERRYMX_1U_SK6812_MINI_E")
      (fields (field (name "CONTRIBUTOR") "Andrea Peron"))
      (libsource (lib "altium-import") (part "root_0_CHERRYMX_1U_SK6812_MINI_E_"))
    )
    (comp (ref "SW86")
      (value "CHERRYMX_1U_SK6812_MINI_E")
      (fields (field (name "CONTRIBUTOR") "Andrea Peron"))
      (libsource (lib "altium-import") (part "root_0_CHERRYMX_1U_SK6812_MINI_E_"))
    )
    (comp (ref "SW87")
      (value "CHERRYMX_1U_SK6812_MINI_E")
      (fields (field (name "CONTRIBUTOR") "Andrea Peron"))
      (libsource (lib "altium-import") (part "root_0_CHERRYMX_1U_SK6812_MINI_E_"))
    )
    (comp (ref "SW88")
      (value "CHERRYMX_1U_SK6812_MINI_E")
      (fields (field (name "CONTRIBUTOR") "Andrea Peron"))
      (libsource (lib "altium-import") (part "root_0_CHERRYMX_1U_SK6812_MINI_E_"))
    )
    (comp (ref "SW89")
      (value "CHERRYMX_1U_SK6812_MINI_E")
      (fields (field (name "CONTRIBUTOR") "Andrea Peron"))
      (libsource (lib "altium-import") (part "root_0_CHERRYMX_1U_SK6812_MINI_E_"))
    )
    (comp (ref "SW91")
      (value "CHERRYMX_1U_SK6812_MINI_E")
      (fields (field (name "CONTRIBUTOR") "Andrea Peron"))
      (libsource (lib "altium-import") (part "root_0_CHERRYMX_1U_SK6812_MINI_E_"))
    )
    (comp (ref "SW92")
      (value "CHERRYMX_1U_SK6812_MINI_E")
      (fields (field (name "CONTRIBUTOR") "Andrea Peron"))
      (libsource (lib "altium-import") (part "root_0_CHERRYMX_1U_SK6812_MINI_E_"))
    )
    (comp (ref "SW93")
      (value "CHERRYMX_1U_SK6812_MINI_E")
      (fields (field (name "CONTRIBUTOR") "Andrea Peron"))
      (libsource (lib "altium-import") (part "root_0_CHERRYMX_1U_SK6812_MINI_E_"))
    )
    (comp (ref "SW94")
      (value "CHERRYMX_1U_SK6812_MINI_E")
      (fields (field (name "CONTRIBUTOR") "Andrea Peron"))
      (libsource (lib "altium-import") (part "root_0_CHERRYMX_1U_SK6812_MINI_E_"))
    )
    (comp (ref "SW95")
      (value "CHERRYMX_1U_SK6812_MINI_E")
      (fields (field (name "CONTRIBUTOR") "Andrea Peron"))
      (libsource (lib "altium-import") (part "root_0_CHERRYMX_1U_SK6812_MINI_E_"))
    )
    (comp (ref "SW96")
      (value "CHERRYMX_1U_SK6812_MINI_E")
      (fields (field (name "CONTRIBUTOR") "Andrea Peron"))
      (libsource (lib "altium-import") (part "root_0_CHERRYMX_1U_SK6812_MINI_E_"))
    )
    (comp (ref "SW97")
      (value "CHERRYMX_1U_SK6812_MINI_E")
      (fields (field (name "CONTRIBUTOR") "Andrea Peron"))
      (libsource (lib "altium-import") (part "root_0_CHERRYMX_1U_SK6812_MINI_E_"))
    )
    (comp (ref "SW98")
      (value "CHERRYMX_1U_SK6812_MINI_E")
      (fields (field (name "CONTRIBUTOR") "Andrea Peron"))
      (libsource (lib "altium-import") (part "root_0_CHERRYMX_1U_SK6812_MINI_E_"))
    )
    (comp (ref "SW99")
      (value "CHERRYMX_1U_SK6812_MINI_E")
      (fields (field (name "CONTRIBUTOR") "Andrea Peron"))
      (libsource (lib "altium-import") (part "root_0_CHERRYMX_1U_SK6812_MINI_E_"))
    )
    (comp (ref "SW100")
      (value "CHERRYMX_1U_SK6812_MINI_E")
      (fields (field (name "CONTRIBUTOR") "Andrea Peron"))
      (libsource (lib "altium-import") (part "root_0_CHERRYMX_1U_SK6812_MINI_E_"))
    )
    (comp (ref "SW101")
      (value "CHERRYMX_1U_SK6812_MINI_E")
      (fields (field (name "CONTRIBUTOR") "Andrea Peron"))
      (libsource (lib "altium-import") (part "root_0_CHERRYMX_1U_SK6812_MINI_E_"))
    )
    (comp (ref "SW102")
      (value "CHERRYMX_1U_SK6812_MINI_E")
      (fields (field (name "CONTRIBUTOR") "Andrea Peron"))
      (libsource (lib "altium-import") (part "root_0_CHERRYMX_1U_SK6812_MINI_E_"))
    )
    (comp (ref "SW104")
      (value "CHERRYMX_1U_SK6812_MINI_E")
      (fields (field (name "CONTRIBUTOR") "Andrea Peron"))
      (libsource (lib "altium-import") (part "root_0_CHERRYMX_1U_SK6812_MINI_E_"))
    )
    (comp (ref "U1")
      (value "PCA9505DGG,118")
      (fields (field (name "MANUFACTURER") "NXP(恩智浦)") (field (name "CONTRIBUTOR") "LCSC"))
      (libsource (lib "altium-import") (part "root_0_PCA9505DGG,118_"))
    )
    (comp (ref "U3")
      (value "XIAO_NRF52840")
      (fields (field (name "CONTRIBUTOR") "Kushal Soni"))
      (libsource (lib "altium-import") (part "root_0_XIAO_NRF52840_"))
    )
    (comp (ref "U4")
      (value "beautiful-solderbridge")
      (fields (field (name "CONTRIBUTOR") "loic.rochat"))
      (libsource (lib "altium-import") (part "root_0_beautiful-solderbridge_"))
    )
    (comp (ref "U5")
      (value "beautiful-solderbridge")
      (fields (field (name "CONTRIBUTOR") "loic.rochat"))
      (libsource (lib "altium-import") (part "root_0_beautiful-solderbridge_"))
    )
    (comp (ref "U6")
      (value "beautiful-solderbridge")
      (fields (field (name "CONTRIBUTOR") "loic.rochat"))
      (libsource (lib "altium-import") (part "root_0_beautiful-solderbridge_"))
    )
    (comp (ref "U7")
      (value "beautiful-solderbridge")
      (fields (field (name "CONTRIBUTOR") "loic.rochat"))
      (libsource (lib "altium-import") (part "root_0_beautiful-solderbridge_"))
    )
    (comp (ref "U8")
      (value "beautiful-solderbridge")
      (fields (field (name "CONTRIBUTOR") "loic.rochat"))
      (libsource (lib "altium-import") (part "root_0_beautiful-solderbridge_"))
    )
    (comp (ref "U9")
      (value "beautiful-solderbridge")
      (fields (field (name "CONTRIBUTOR") "loic.rochat"))
      (libsource (lib "altium-import") (part "root_0_beautiful-solderbridge_"))
    )
    (comp (ref "U10")
      (value "PCA9505DGG,118")
      (fields (field (name "MANUFACTURER") "NXP(恩智浦)") (field (name "CONTRIBUTOR") "LCSC"))
      (libsource (lib "altium-import") (part "root_0_PCA9505DGG,118_"))
    )
    (comp (ref "U11")
      (value "beautiful-solderbridge")
      (fields (field (name "CONTRIBUTOR") "loic.rochat"))
      (libsource (lib "altium-import") (part "root_0_beautiful-solderbridge_"))
    )
    (comp (ref "U12")
      (value "beautiful-solderbridge")
      (fields (field (name "CONTRIBUTOR") "loic.rochat"))
      (libsource (lib "altium-import") (part "root_0_beautiful-solderbridge_"))
    )
    (comp (ref "U13")
      (value "beautiful-solderbridge")
      (fields (field (name "CONTRIBUTOR") "loic.rochat"))
      (libsource (lib "altium-import") (part "root_0_beautiful-solderbridge_"))
    )
    (comp (ref "U14")
      (value "beautiful-solderbridge")
      (fields (field (name "CONTRIBUTOR") "loic.rochat"))
      (libsource (lib "altium-import") (part "root_0_beautiful-solderbridge_"))
    )
    (comp (ref "U15")
      (value "beautiful-solderbridge")
      (fields (field (name "CONTRIBUTOR") "loic.rochat"))
      (libsource (lib "altium-import") (part "root_0_beautiful-solderbridge_"))
    )
    (comp (ref "U16")
      (value "beautiful-solderbridge")
      (fields (field (name "CONTRIBUTOR") "loic.rochat"))
      (libsource (lib "altium-import") (part "root_0_beautiful-solderbridge_"))
    )
    (comp (ref "U17")
      (value "beautiful-solderbridge")
      (fields (field (name "CONTRIBUTOR") "loic.rochat"))
      (libsource (lib "altium-import") (part "root_0_beautiful-solderbridge_"))
    )
    (comp (ref "U18")
      (value "beautiful-solderbridge")
      (fields (field (name "CONTRIBUTOR") "loic.rochat"))
      (libsource (lib "altium-import") (part "root_0_beautiful-solderbridge_"))
    )
    (comp (ref "U19")
      (value "beautiful-solderbridge")
      (fields (field (name "CONTRIBUTOR") "loic.rochat"))
      (libsource (lib "altium-import") (part "root_0_beautiful-solderbridge_"))
    )
    (comp (ref "U20")
      (value "beautiful-solderbridge")
      (fields (field (name "CONTRIBUTOR") "loic.rochat"))
      (libsource (lib "altium-import") (part "root_0_beautiful-solderbridge_"))
    )
    (comp (ref "U21")
      (value "beautiful-solderbridge")
      (fields (field (name "CONTRIBUTOR") "loic.rochat"))
      (libsource (lib "altium-import") (part "root_0_beautiful-solderbridge_"))
    )
    (comp (ref "U22")
      (value "beautiful-solderbridge")
      (fields (field (name "CONTRIBUTOR") "loic.rochat"))
      (libsource (lib "altium-import") (part "root_0_beautiful-solderbridge_"))
    )
    (comp (ref "U23")
      (value "PCA9505DGG,118")
      (fields (field (name "MANUFACTURER") "NXP(恩智浦)") (field (name "CONTRIBUTOR") "LCSC"))
      (libsource (lib "altium-import") (part "root_0_PCA9505DGG,118_"))
    )
  )
  (nets
    (net (code "1") (name "/1_A0") (class "Default")
      (node (ref "U1") (pin "27") (pinfunction "A0_27") (pintype "passive"))
      (node (ref "U4") (pin "1") (pinfunction "1_1") (pintype "passive"))
      (node (ref "U5") (pin "1") (pinfunction "1_1") (pintype "passive"))
    )
    (net (code "2") (name "/1_A1") (class "Default")
      (node (ref "U1") (pin "28") (pinfunction "A1_28") (pintype "passive"))
      (node (ref "U6") (pin "1") (pinfunction "1_1") (pintype "passive"))
      (node (ref "U7") (pin "1") (pinfunction "1_1") (pintype "passive"))
    )
    (net (code "3") (name "/1_A2") (class "Default")
      (node (ref "U1") (pin "29") (pinfunction "A2_29") (pintype "passive"))
      (node (ref "U8") (pin "1") (pinfunction "1_1") (pintype "passive"))
      (node (ref "U9") (pin "1") (pinfunction "1_1") (pintype "passive"))
    )
    (net (code "4") (name "/1_INT_PCA") (class "Default")
      (node (ref "R5") (pin "2") (pinfunction "2_2") (pintype "passive"))
      (node (ref "U1") (pin "55") (pinfunction "INT#_55") (pintype "passive"))
    )
    (net (code "5") (name "/1_IO_0_0") (class "Default")
      (node (ref "SW0") (pin "SW1") (pinfunction "SW1_SW1") (pintype "passive"))
      (node (ref "U1") (pin "3") (pinfunction "IO0_0_3") (pintype "passive"))
    )
    (net (code "6") (name "/1_IO_0_1") (class "Default")
      (node (ref "SW1") (pin "SW1") (pinfunction "SW1_SW1") (pintype "passive"))
      (node (ref "U1") (pin "4") (pinfunction "IO0_1_4") (pintype "passive"))
    )
    (net (code "7") (name "/1_IO_0_2") (class "Default")
      (node (ref "SW2") (pin "SW1") (pinfunction "SW1_SW1") (pintype "passive"))
      (node (ref "U1") (pin "5") (pinfunction "IO0_2_5") (pintype "passive"))
    )
    (net (code "8") (name "/1_IO_0_3") (class "Default")
      (node (ref "SW3") (pin "SW1") (pinfunction "SW1_SW1") (pintype "passive"))
      (node (ref "U1") (pin "7") (pinfunction "IO0_3_7") (pintype "passive"))
    )
    (net (code "9") (name "/1_IO_0_4") (class "Default")
      (node (ref "SW4") (pin "SW1") (pinfunction "SW1_SW1") (pintype "passive"))
      (node (ref "U1") (pin "8") (pinfunction "IO0_4_8") (pintype "passive"))
    )
    (net (code "10") (name "/1_IO_0_5") (class "Default")
      (node (ref "SW5") (pin "SW1") (pinfunction "SW1_SW1") (pintype "passive"))
      (node (ref "U1") (pin "9") (pinfunction "IO0_5_9") (pintype "passive"))
    )
    (net (code "11") (name "/1_IO_0_6") (class "Default")
      (node (ref "SW10") (pin "SW1") (pinfunction "SW1_SW1") (pintype "passive"))
      (node (ref "U1") (pin "10") (pinfunction "IO0_6_10") (pintype "passive"))
    )
    (net (code "12") (name "/1_IO_0_7") (class "Default")
      (node (ref "SW8") (pin "SW1") (pinfunction "SW1_SW1") (pintype "passive"))
      (node (ref "U1") (pin "12") (pinfunction "IO0_7_12") (pintype "passive"))
    )
    (net (code "13") (name "/1_IO_1_0") (class "Default")
      (node (ref "SW9") (pin "SW1") (pinfunction "SW1_SW1") (pintype "passive"))
      (node (ref "U1") (pin "13") (pinfunction "IO1_0_13") (pintype "passive"))
    )
    (net (code "14") (name "/1_IO_1_1") (class "Default")
      (node (ref "SW6") (pin "SW1") (pinfunction "SW1_SW1") (pintype "passive"))
      (node (ref "U1") (pin "14") (pinfunction "IO1_1_14") (pintype "passive"))
    )
    (net (code "15") (name "/1_IO_1_2") (class "Default")
      (node (ref "SW7") (pin "SW1") (pinfunction "SW1_SW1") (pintype "passive"))
      (node (ref "U1") (pin "15") (pinfunction "IO1_2_15") (pintype "passive"))
    )
    (net (code "16") (name "/1_IO_1_3") (class "Default")
      (node (ref "SW23") (pin "SW1") (pinfunction "SW1_SW1") (pintype "passive"))
      (node (ref "U1") (pin "16") (pinfunction "IO1_3_16") (pintype "passive"))
    )
    (net (code "17") (name "/1_IO_1_4") (class "Default")
      (node (ref "SW22") (pin "SW1") (pinfunction "SW1_SW1") (pintype "passive"))
      (node (ref "U1") (pin "17") (pinfunction "IO1_4_17") (pintype "passive"))
    )
    (net (code "18") (name "/1_IO_1_5") (class "Default")
      (node (ref "SW20") (pin "SW1") (pinfunction "SW1_SW1") (pintype "passive"))
      (node (ref "U1") (pin "19") (pinfunction "IO1_5_19") (pintype "passive"))
    )
    (net (code "19") (name "/1_IO_1_6") (class "Default")
      (node (ref "SW21") (pin "SW1") (pinfunction "SW1_SW1") (pintype "passive"))
      (node (ref "U1") (pin "20") (pinfunction "IO1_6_20") (pintype "passive"))
    )
    (net (code "20") (name "/1_IO_1_7") (class "Default")
      (node (ref "SW18") (pin "SW1") (pinfunction "SW1_SW1") (pintype "passive"))
      (node (ref "U1") (pin "21") (pinfunction "IO1_7_21") (pintype "passive"))
    )
    (net (code "21") (name "/1_IO_2_0") (class "Default")
      (node (ref "SW19") (pin "SW1") (pinfunction "SW1_SW1") (pintype "passive"))
      (node (ref "U1") (pin "22") (pinfunction "IO2_0_22") (pintype "passive"))
    )
    (net (code "22") (name "/1_IO_2_1") (class "Default")
      (node (ref "SW12") (pin "SW1") (pinfunction "SW1_SW1") (pintype "passive"))
      (node (ref "U1") (pin "24") (pinfunction "IO2_1_24") (pintype "passive"))
    )
    (net (code "23") (name "/1_IO_2_2") (class "Default")
      (node (ref "SW13") (pin "SW1") (pinfunction "SW1_SW1") (pintype "passive"))
      (node (ref "U1") (pin "25") (pinfunction "IO2_2_25") (pintype "passive"))
    )
    (net (code "24") (name "/1_IO_2_3") (class "Default")
      (node (ref "SW15") (pin "SW1") (pinfunction "SW1_SW1") (pintype "passive"))
      (node (ref "U1") (pin "26") (pinfunction "IO2_3_26") (pintype "passive"))
    )
    (net (code "25") (name "/1_IO_2_4") (class "Default")
      (node (ref "SW14") (pin "SW1") (pinfunction "SW1_SW1") (pintype "passive"))
      (node (ref "U1") (pin "31") (pinfunction "IO2_4_31") (pintype "passive"))
    )
    (net (code "26") (name "/1_IO_2_5") (class "Default")
      (node (ref "SW17") (pin "SW1") (pinfunction "SW1_SW1") (pintype "passive"))
      (node (ref "U1") (pin "32") (pinfunction "IO2_5_32") (pintype "passive"))
    )
    (net (code "27") (name "/1_IO_2_6") (class "Default")
      (node (ref "SW16") (pin "SW1") (pinfunction "SW1_SW1") (pintype "passive"))
      (node (ref "U1") (pin "33") (pinfunction "IO2_6_33") (pintype "passive"))
    )
    (net (code "28") (name "/1_IO_2_7") (class "Default")
      (node (ref "SW11") (pin "SW1") (pinfunction "SW1_SW1") (pintype "passive"))
      (node (ref "U1") (pin "35") (pinfunction "IO2_7_35") (pintype "passive"))
    )
    (net (code "29") (name "/1_IO_3_0") (class "Default")
      (node (ref "SW24") (pin "SW1") (pinfunction "SW1_SW1") (pintype "passive"))
      (node (ref "U1") (pin "36") (pinfunction "IO3_0_36") (pintype "passive"))
    )
    (net (code "30") (name "/1_IO_3_1") (class "Default")
      (node (ref "SW26") (pin "SW1") (pinfunction "SW1_SW1") (pintype "passive"))
      (node (ref "U1") (pin "37") (pinfunction "IO3_1_37") (pintype "passive"))
    )
    (net (code "31") (name "/1_IO_3_2") (class "Default")
      (node (ref "SW25") (pin "SW1") (pinfunction "SW1_SW1") (pintype "passive"))
      (node (ref "U1") (pin "38") (pinfunction "IO3_2_38") (pintype "passive"))
    )
    (net (code "32") (name "/1_IO_3_3") (class "Default")
      (node (ref "SW28") (pin "SW1") (pinfunction "SW1_SW1") (pintype "passive"))
      (node (ref "U1") (pin "40") (pinfunction "IO3_3_40") (pintype "passive"))
    )
    (net (code "33") (name "/1_IO_3_4") (class "Default")
      (node (ref "SW34") (pin "SW1") (pinfunction "SW1_SW1") (pintype "passive"))
      (node (ref "U1") (pin "41") (pinfunction "IO3_4_41") (pintype "passive"))
    )
    (net (code "34") (name "/1_IO_3_5") (class "Default")
      (node (ref "SW33") (pin "SW1") (pinfunction "SW1_SW1") (pintype "passive"))
      (node (ref "U1") (pin "42") (pinfunction "IO3_5_42") (pintype "passive"))
    )
    (net (code "35") (name "/1_IO_3_6") (class "Default")
      (node (ref "SW31") (pin "SW1") (pinfunction "SW1_SW1") (pintype "passive"))
      (node (ref "U1") (pin "43") (pinfunction "IO3_6_43") (pintype "passive"))
    )
    (net (code "36") (name "/1_IO_3_7") (class "Default")
      (node (ref "SW32") (pin "SW1") (pinfunction "SW1_SW1") (pintype "passive"))
      (node (ref "U1") (pin "44") (pinfunction "IO3_7_44") (pintype "passive"))
    )
    (net (code "37") (name "/1_IO_4_0") (class "Default")
      (node (ref "SW29") (pin "SW1") (pinfunction "SW1_SW1") (pintype "passive"))
      (node (ref "U1") (pin "45") (pinfunction "IO4_0_45") (pintype "passive"))
    )
    (net (code "38") (name "/1_IO_4_1") (class "Default")
      (node (ref "SW35") (pin "SW1") (pinfunction "SW1_SW1") (pintype "passive"))
      (node (ref "U1") (pin "47") (pinfunction "IO4_1_47") (pintype "passive"))
    )
    (net (code "39") (name "/1_IO_4_2") (class "Default")
      (node (ref "SW36") (pin "SW1") (pinfunction "SW1_SW1") (pintype "passive"))
      (node (ref "U1") (pin "48") (pinfunction "IO4_2_48") (pintype "passive"))
    )
    (net (code "40") (name "/1_IO_4_3") (class "Default")
      (node (ref "SW38") (pin "SW1") (pinfunction "SW1_SW1") (pintype "passive"))
      (node (ref "U1") (pin "49") (pinfunction "IO4_3_49") (pintype "passive"))
    )
    (net (code "41") (name "/1_IO_4_4") (class "Default")
      (node (ref "SW37") (pin "SW1") (pinfunction "SW1_SW1") (pintype "passive"))
      (node (ref "U1") (pin "50") (pinfunction "IO4_4_50") (pintype "passive"))
    )
    (net (code "42") (name "/1_IO_4_5") (class "Default")
      (node (ref "SW40") (pin "SW1") (pinfunction "SW1_SW1") (pintype "passive"))
      (node (ref "U1") (pin "52") (pinfunction "IO4_5_52") (pintype "passive"))
    )
    (net (code "43") (name "/1_IO_4_6") (class "Default")
      (node (ref "SW46") (pin "SW1") (pinfunction "SW1_SW1") (pintype "passive"))
      (node (ref "U1") (pin "53") (pinfunction "IO4_6_53") (pintype "passive"))
    )
    (net (code "44") (name "/1_IO_4_7") (class "Default")
      (node (ref "SW45") (pin "SW1") (pinfunction "SW1_SW1") (pintype "passive"))
      (node (ref "U1") (pin "54") (pinfunction "IO4_7_54") (pintype "passive"))
    )
    (net (code "45") (name "/1_OE_PCA") (class "Default")
      (node (ref "R3") (pin "2") (pinfunction "2_2") (pintype "passive"))
      (node (ref "U1") (pin "30") (pinfunction "OE#_30") (pintype "passive"))
    )
    (net (code "46") (name "/1_RESET_PCA") (class "Default")
      (node (ref "R4") (pin "2") (pinfunction "2_2") (pintype "passive"))
      (node (ref "U1") (pin "56") (pinfunction "RESET#_56") (pintype "passive"))
    )
    (net (code "47") (name "/2_A0") (class "Default")
      (node (ref "U10") (pin "27") (pinfunction "A0_27") (pintype "passive"))
      (node (ref "U15") (pin "1") (pinfunction "1_1") (pintype "passive"))
      (node (ref "U16") (pin "1") (pinfunction "1_1") (pintype "passive"))
    )
    (net (code "48") (name "/2_A1") (class "Default")
      (node (ref "U10") (pin "28") (pinfunction "A1_28") (pintype "passive"))
      (node (ref "U13") (pin "1") (pinfunction "1_1") (pintype "passive"))
      (node (ref "U14") (pin "1") (pinfunction "1_1") (pintype "passive"))
    )
    (net (code "49") (name "/2_A2") (class "Default")
      (node (ref "U10") (pin "29") (pinfunction "A2_29") (pintype "passive"))
      (node (ref "U11") (pin "1") (pinfunction "1_1") (pintype "passive"))
      (node (ref "U12") (pin "1") (pinfunction "1_1") (pintype "passive"))
    )
    (net (code "50") (name "/2_INT_PCA") (class "Default")
      (node (ref "R8") (pin "2") (pinfunction "2_2") (pintype "passive"))
      (node (ref "U10") (pin "55") (pinfunction "INT#_55") (pintype "passive"))
    )
    (net (code "51") (name "/2_IO_0_0") (class "Default")
      (node (ref "SW43") (pin "SW1") (pinfunction "SW1_SW1") (pintype "passive"))
      (node (ref "U10") (pin "3") (pinfunction "IO0_0_3") (pintype "passive"))
    )
    (net (code "52") (name "/2_IO_0_1") (class "Default")
      (node (ref "SW44") (pin "SW1") (pinfunction "SW1_SW1") (pintype "passive"))
      (node (ref "U10") (pin "4") (pinfunction "IO0_1_4") (pintype "passive"))
    )
    (net (code "53") (name "/2_IO_0_2") (class "Default")
      (node (ref "SW41") (pin "SW1") (pinfunction "SW1_SW1") (pintype "passive"))
      (node (ref "U10") (pin "5") (pinfunction "IO0_2_5") (pintype "passive"))
    )
    (net (code "54") (name "/2_IO_0_3") (class "Default")
      (node (ref "SW42") (pin "SW1") (pinfunction "SW1_SW1") (pintype "passive"))
      (node (ref "U10") (pin "7") (pinfunction "IO0_3_7") (pintype "passive"))
    )
    (net (code "55") (name "/2_IO_0_4") (class "Default")
      (node (ref "SW47") (pin "SW1") (pinfunction "SW1_SW1") (pintype "passive"))
      (node (ref "U10") (pin "8") (pinfunction "IO0_4_8") (pintype "passive"))
    )
    (net (code "56") (name "/2_IO_0_5") (class "Default")
      (node (ref "SW48") (pin "SW1") (pinfunction "SW1_SW1") (pintype "passive"))
      (node (ref "U10") (pin "9") (pinfunction "IO0_5_9") (pintype "passive"))
    )
    (net (code "57") (name "/2_IO_0_6") (class "Default")
      (node (ref "SW50") (pin "SW1") (pinfunction "SW1_SW1") (pintype "passive"))
      (node (ref "U10") (pin "10") (pinfunction "IO0_6_10") (pintype "passive"))
    )
    (net (code "58") (name "/2_IO_0_7") (class "Default")
      (node (ref "SW49") (pin "SW1") (pinfunction "SW1_SW1") (pintype "passive"))
      (node (ref "U10") (pin "12") (pinfunction "IO0_7_12") (pintype "passive"))
    )
    (net (code "59") (name "/2_IO_1_0") (class "Default")
      (node (ref "SW52") (pin "SW1") (pinfunction "SW1_SW1") (pintype "passive"))
      (node (ref "U10") (pin "13") (pinfunction "IO1_0_13") (pintype "passive"))
    )
    (net (code "60") (name "/2_IO_1_1") (class "Default")
      (node (ref "SW58") (pin "SW1") (pinfunction "SW1_SW1") (pintype "passive"))
      (node (ref "U10") (pin "14") (pinfunction "IO1_1_14") (pintype "passive"))
    )
    (net (code "61") (name "/2_IO_1_2") (class "Default")
      (node (ref "SW57") (pin "SW1") (pinfunction "SW1_SW1") (pintype "passive"))
      (node (ref "U10") (pin "15") (pinfunction "IO1_2_15") (pintype "passive"))
    )
    (net (code "62") (name "/2_IO_1_3") (class "Default")
      (node (ref "SW55") (pin "SW1") (pinfunction "SW1_SW1") (pintype "passive"))
      (node (ref "U10") (pin "16") (pinfunction "IO1_3_16") (pintype "passive"))
    )
    (net (code "63") (name "/2_IO_1_4") (class "Default")
      (node (ref "SW56") (pin "SW1") (pinfunction "SW1_SW1") (pintype "passive"))
      (node (ref "U10") (pin "17") (pinfunction "IO1_4_17") (pintype "passive"))
    )
    (net (code "64") (name "/2_IO_1_5") (class "Default")
      (node (ref "SW53") (pin "SW1") (pinfunction "SW1_SW1") (pintype "passive"))
      (node (ref "U10") (pin "19") (pinfunction "IO1_5_19") (pintype "passive"))
    )
    (net (code "65") (name "/2_IO_1_6") (class "Default")
      (node (ref "SW59") (pin "SW1") (pinfunction "SW1_SW1") (pintype "passive"))
      (node (ref "U10") (pin "20") (pinfunction "IO1_6_20") (pintype "passive"))
    )
    (net (code "66") (name "/2_IO_1_7") (class "Default")
      (node (ref "SW60") (pin "SW1") (pinfunction "SW1_SW1") (pintype "passive"))
      (node (ref "U10") (pin "21") (pinfunction "IO1_7_21") (pintype "passive"))
    )
    (net (code "67") (name "/2_IO_2_0") (class "Default")
      (node (ref "SW62") (pin "SW1") (pinfunction "SW1_SW1") (pintype "passive"))
      (node (ref "U10") (pin "22") (pinfunction "IO2_0_22") (pintype "passive"))
    )
    (net (code "68") (name "/2_IO_2_1") (class "Default")
      (node (ref "SW61") (pin "SW1") (pinfunction "SW1_SW1") (pintype "passive"))
      (node (ref "U10") (pin "24") (pinfunction "IO2_1_24") (pintype "passive"))
    )
    (net (code "69") (name "/2_IO_2_2") (class "Default")
      (node (ref "SW64") (pin "SW1") (pinfunction "SW1_SW1") (pintype "passive"))
      (node (ref "U10") (pin "25") (pinfunction "IO2_2_25") (pintype "passive"))
    )
    (net (code "70") (name "/2_IO_2_3") (class "Default")
      (node (ref "SW70") (pin "SW1") (pinfunction "SW1_SW1") (pintype "passive"))
      (node (ref "U10") (pin "26") (pinfunction "IO2_3_26") (pintype "passive"))
    )
    (net (code "71") (name "/2_IO_2_4") (class "Default")
      (node (ref "SW69") (pin "SW1") (pinfunction "SW1_SW1") (pintype "passive"))
      (node (ref "U10") (pin "31") (pinfunction "IO2_4_31") (pintype "passive"))
    )
    (net (code "72") (name "/2_IO_2_5") (class "Default")
      (node (ref "SW67") (pin "SW1") (pinfunction "SW1_SW1") (pintype "passive"))
      (node (ref "U10") (pin "32") (pinfunction "IO2_5_32") (pintype "passive"))
    )
    (net (code "73") (name "/2_IO_2_6") (class "Default")
      (node (ref "SW68") (pin "SW1") (pinfunction "SW1_SW1") (pintype "passive"))
      (node (ref "U10") (pin "33") (pinfunction "IO2_6_33") (pintype "passive"))
    )
    (net (code "74") (name "/2_IO_2_7") (class "Default")
      (node (ref "SW65") (pin "SW1") (pinfunction "SW1_SW1") (pintype "passive"))
      (node (ref "U10") (pin "35") (pinfunction "IO2_7_35") (pintype "passive"))
    )
    (net (code "75") (name "/2_IO_3_0") (class "Default")
      (node (ref "SW66") (pin "SW1") (pinfunction "SW1_SW1") (pintype "passive"))
      (node (ref "U10") (pin "36") (pinfunction "IO3_0_36") (pintype "passive"))
    )
    (net (code "76") (name "/2_IO_3_1") (class "Default")
      (node (ref "SW71") (pin "SW1") (pinfunction "SW1_SW1") (pintype "passive"))
      (node (ref "U10") (pin "37") (pinfunction "IO3_1_37") (pintype "passive"))
    )
    (net (code "77") (name "/2_IO_3_2") (class "Default")
      (node (ref "SW72") (pin "SW1") (pinfunction "SW1_SW1") (pintype "passive"))
      (node (ref "U10") (pin "38") (pinfunction "IO3_2_38") (pintype "passive"))
    )
    (net (code "78") (name "/2_IO_3_3") (class "Default")
      (node (ref "SW74") (pin "SW1") (pinfunction "SW1_SW1") (pintype "passive"))
      (node (ref "U10") (pin "40") (pinfunction "IO3_3_40") (pintype "passive"))
    )
    (net (code "79") (name "/2_IO_3_4") (class "Default")
      (node (ref "SW73") (pin "SW1") (pinfunction "SW1_SW1") (pintype "passive"))
      (node (ref "U10") (pin "41") (pinfunction "IO3_4_41") (pintype "passive"))
    )
    (net (code "80") (name "/2_IO_3_5") (class "Default")
      (node (ref "SW76") (pin "SW1") (pinfunction "SW1_SW1") (pintype "passive"))
      (node (ref "U10") (pin "42") (pinfunction "IO3_5_42") (pintype "passive"))
    )
    (net (code "81") (name "/2_IO_3_6") (class "Default")
      (node (ref "SW75") (pin "SW1") (pinfunction "SW1_SW1") (pintype "passive"))
      (node (ref "U10") (pin "43") (pinfunction "IO3_6_43") (pintype "passive"))
    )
    (net (code "82") (name "/2_IO_3_7") (class "Default")
      (node (ref "SW82") (pin "SW1") (pinfunction "SW1_SW1") (pintype "passive"))
      (node (ref "U10") (pin "44") (pinfunction "IO3_7_44") (pintype "passive"))
    )
    (net (code "83") (name "/2_IO_4_0") (class "Default")
      (node (ref "SW81") (pin "SW1") (pinfunction "SW1_SW1") (pintype "passive"))
      (node (ref "U10") (pin "45") (pinfunction "IO4_0_45") (pintype "passive"))
    )
    (net (code "84") (name "/2_IO_4_1") (class "Default")
      (node (ref "SW80") (pin "SW1") (pinfunction "SW1_SW1") (pintype "passive"))
      (node (ref "U10") (pin "47") (pinfunction "IO4_1_47") (pintype "passive"))
    )
    (net (code "85") (name "/2_IO_4_2") (class "Default")
      (node (ref "SW78") (pin "SW1") (pinfunction "SW1_SW1") (pintype "passive"))
      (node (ref "U10") (pin "48") (pinfunction "IO4_2_48") (pintype "passive"))
    )
    (net (code "86") (name "/2_IO_4_3") (class "Default")
      (node (ref "SW83") (pin "SW1") (pinfunction "SW1_SW1") (pintype "passive"))
      (node (ref "U10") (pin "49") (pinfunction "IO4_3_49") (pintype "passive"))
    )
    (net (code "87") (name "/2_IO_4_4") (class "Default")
      (node (ref "SW84") (pin "SW1") (pinfunction "SW1_SW1") (pintype "passive"))
      (node (ref "U10") (pin "50") (pinfunction "IO4_4_50") (pintype "passive"))
    )
    (net (code "88") (name "/2_IO_4_5") (class "Default")
      (node (ref "SW86") (pin "SW1") (pinfunction "SW1_SW1") (pintype "passive"))
      (node (ref "U10") (pin "52") (pinfunction "IO4_5_52") (pintype "passive"))
    )
    (net (code "89") (name "/2_IO_4_6") (class "Default")
      (node (ref "SW85") (pin "SW1") (pinfunction "SW1_SW1") (pintype "passive"))
      (node (ref "U10") (pin "53") (pinfunction "IO4_6_53") (pintype "passive"))
    )
    (net (code "90") (name "/2_IO_4_7") (class "Default")
      (node (ref "SW88") (pin "SW1") (pinfunction "SW1_SW1") (pintype "passive"))
      (node (ref "U10") (pin "54") (pinfunction "IO4_7_54") (pintype "passive"))
    )
    (net (code "91") (name "/2_OE_PCA") (class "Default")
      (node (ref "R10") (pin "2") (pinfunction "2_2") (pintype "passive"))
      (node (ref "U10") (pin "30") (pinfunction "OE#_30") (pintype "passive"))
    )
    (net (code "92") (name "/2_RESET_PCA") (class "Default")
      (node (ref "R9") (pin "2") (pinfunction "2_2") (pintype "passive"))
      (node (ref "U10") (pin "56") (pinfunction "RESET#_56") (pintype "passive"))
    )
    (net (code "93") (name "/3V3_PCA") (class "Default")
      (node (ref "H1") (pin "5") (pinfunction "5_5") (pintype "passive"))
      (node (ref "Q1") (pin "1") (pinfunction "G_1") (pintype "passive"))
      (node (ref "R17") (pin "2") (pinfunction "2_2") (pintype "passive"))
      (node (ref "U3") (pin "12") (pinfunction "3V3_12") (pintype "passive"))
    )
    (net (code "94") (name "/3_A0") (class "Default")
      (node (ref "U17") (pin "1") (pinfunction "1_1") (pintype "passive"))
      (node (ref "U18") (pin "1") (pinfunction "1_1") (pintype "passive"))
      (node (ref "U23") (pin "27") (pinfunction "A0_27") (pintype "passive"))
    )
    (net (code "95") (name "/3_A1") (class "Default")
      (node (ref "U19") (pin "1") (pinfunction "1_1") (pintype "passive"))
      (node (ref "U20") (pin "1") (pinfunction "1_1") (pintype "passive"))
      (node (ref "U23") (pin "28") (pinfunction "A1_28") (pintype "passive"))
    )
    (net (code "96") (name "/3_A2") (class "Default")
      (node (ref "U21") (pin "1") (pinfunction "1_1") (pintype "passive"))
      (node (ref "U22") (pin "1") (pinfunction "1_1") (pintype "passive"))
      (node (ref "U23") (pin "29") (pinfunction "A2_29") (pintype "passive"))
    )
    (net (code "97") (name "/3_INT_PCA") (class "Default")
      (node (ref "R13") (pin "2") (pinfunction "2_2") (pintype "passive"))
      (node (ref "U23") (pin "55") (pinfunction "INT#_55") (pintype "passive"))
    )
    (net (code "98") (name "/3_IO_0_0") (class "Default")
      (node (ref "SW87") (pin "SW1") (pinfunction "SW1_SW1") (pintype "passive"))
      (node (ref "U23") (pin "3") (pinfunction "IO0_0_3") (pintype "passive"))
    )
    (net (code "99") (name "/3_IO_0_1") (class "Default")
      (node (ref "SW94") (pin "SW1") (pinfunction "SW1_SW1") (pintype "passive"))
      (node (ref "U23") (pin "4") (pinfunction "IO0_1_4") (pintype "passive"))
    )
    (net (code "100") (name "/3_IO_0_2") (class "Default")
      (node (ref "SW93") (pin "SW1") (pinfunction "SW1_SW1") (pintype "passive"))
      (node (ref "U23") (pin "5") (pinfunction "IO0_2_5") (pintype "passive"))
    )
    (net (code "101") (name "/3_IO_0_3") (class "Default")
      (node (ref "SW91") (pin "SW1") (pinfunction "SW1_SW1") (pintype "passive"))
      (node (ref "U23") (pin "7") (pinfunction "IO0_3_7") (pintype "passive"))
    )
    (net (code "102") (name "/3_IO_0_4") (class "Default")
      (node (ref "SW92") (pin "SW1") (pinfunction "SW1_SW1") (pintype "passive"))
      (node (ref "U23") (pin "8") (pinfunction "IO0_4_8") (pintype "passive"))
    )
    (net (code "103") (name "/3_IO_0_5") (class "Default")
      (node (ref "SW89") (pin "SW1") (pinfunction "SW1_SW1") (pintype "passive"))
      (node (ref "U23") (pin "9") (pinfunction "IO0_5_9") (pintype "passive"))
    )
    (net (code "104") (name "/3_IO_0_6") (class "Default")
      (node (ref "SW95") (pin "SW1") (pinfunction "SW1_SW1") (pintype "passive"))
      (node (ref "U23") (pin "10") (pinfunction "IO0_6_10") (pintype "passive"))
    )
    (net (code "105") (name "/3_IO_0_7") (class "Default")
      (node (ref "SW96") (pin "SW1") (pinfunction "SW1_SW1") (pintype "passive"))
      (node (ref "U23") (pin "12") (pinfunction "IO0_7_12") (pintype "passive"))
    )
    (net (code "106") (name "/3_IO_1_0") (class "Default")
      (node (ref "SW98") (pin "SW1") (pinfunction "SW1_SW1") (pintype "passive"))
      (node (ref "U23") (pin "13") (pinfunction "IO1_0_13") (pintype "passive"))
    )
    (net (code "107") (name "/3_IO_1_1") (class "Default")
      (node (ref "SW97") (pin "SW1") (pinfunction "SW1_SW1") (pintype "passive"))
      (node (ref "U23") (pin "14") (pinfunction "IO1_1_14") (pintype "passive"))
    )
    (net (code "108") (name "/3_IO_1_2") (class "Default")
      (node (ref "SW100") (pin "SW1") (pinfunction "SW1_SW1") (pintype "passive"))
      (node (ref "U23") (pin "15") (pinfunction "IO1_2_15") (pintype "passive"))
    )
    (net (code "109") (name "/3_IO_1_3") (class "Default")
      (node (ref "SW99") (pin "SW1") (pinfunction "SW1_SW1") (pintype "passive"))
      (node (ref "U23") (pin "16") (pinfunction "IO1_3_16") (pintype "passive"))
    )
    (net (code "110") (name "/3_IO_1_4") (class "Default")
      (node (ref "SW104") (pin "SW1") (pinfunction "SW1_SW1") (pintype "passive"))
      (node (ref "U23") (pin "17") (pinfunction "IO1_4_17") (pintype "passive"))
    )
    (net (code "111") (name "/3_IO_1_5") (class "Default")
      (node (ref "SW101") (pin "SW1") (pinfunction "SW1_SW1") (pintype "passive"))
      (node (ref "U23") (pin "19") (pinfunction "IO1_5_19") (pintype "passive"))
    )
    (net (code "112") (name "/3_IO_1_6") (class "Default")
      (node (ref "SW102") (pin "SW1") (pinfunction "SW1_SW1") (pintype "passive"))
      (node (ref "U23") (pin "20") (pinfunction "IO1_6_20") (pintype "passive"))
    )
    (net (code "113") (name "/3_IO_1_7") (class "Default")
      (node (ref "U23") (pin "21") (pinfunction "IO1_7_21") (pintype "passive"))
    )
    (net (code "114") (name "/3_IO_2_0") (class "Default")
      (node (ref "U23") (pin "22") (pinfunction "IO2_0_22") (pintype "passive"))
    )
    (net (code "115") (name "/3_IO_2_1") (class "Default")
      (node (ref "U23") (pin "24") (pinfunction "IO2_1_24") (pintype "passive"))
    )
    (net (code "116") (name "/3_IO_2_2") (class "Default")
      (node (ref "U23") (pin "25") (pinfunction "IO2_2_25") (pintype "passive"))
    )
    (net (code "117") (name "/3_IO_2_3") (class "Default")
      (node (ref "U23") (pin "26") (pinfunction "IO2_3_26") (pintype "passive"))
    )
    (net (code "118") (name "/3_IO_2_4") (class "Default")
      (node (ref "U23") (pin "31") (pinfunction "IO2_4_31") (pintype "passive"))
    )
    (net (code "119") (name "/3_IO_2_5") (class "Default")
      (node (ref "U23") (pin "32") (pinfunction "IO2_5_32") (pintype "passive"))
    )
    (net (code "120") (name "/3_IO_2_6") (class "Default")
      (node (ref "U23") (pin "33") (pinfunction "IO2_6_33") (pintype "passive"))
    )
    (net (code "121") (name "/3_IO_2_7") (class "Default")
      (node (ref "U23") (pin "35") (pinfunction "IO2_7_35") (pintype "passive"))
    )
    (net (code "122") (name "/3_IO_3_0") (class "Default")
      (node (ref "U23") (pin "36") (pinfunction "IO3_0_36") (pintype "passive"))
    )
    (net (code "123") (name "/3_IO_3_1") (class "Default")
      (node (ref "U23") (pin "37") (pinfunction "IO3_1_37") (pintype "passive"))
    )
    (net (code "124") (name "/3_IO_3_2") (class "Default")
      (node (ref "U23") (pin "38") (pinfunction "IO3_2_38") (pintype "passive"))
    )
    (net (code "125") (name "/3_IO_3_3") (class "Default")
      (node (ref "U23") (pin "40") (pinfunction "IO3_3_40") (pintype "passive"))
    )
    (net (code "126") (name "/3_IO_3_4") (class "Default")
      (node (ref "U23") (pin "41") (pinfunction "IO3_4_41") (pintype "passive"))
    )
    (net (code "127") (name "/3_IO_3_5") (class "Default")
      (node (ref "U23") (pin "42") (pinfunction "IO3_5_42") (pintype "passive"))
    )
    (net (code "128") (name "/3_IO_3_6") (class "Default")
      (node (ref "U23") (pin "43") (pinfunction "IO3_6_43") (pintype "passive"))
    )
    (net (code "129") (name "/3_IO_3_7") (class "Default")
      (node (ref "U23") (pin "44") (pinfunction "IO3_7_44") (pintype "passive"))
    )
    (net (code "130") (name "/3_IO_4_0") (class "Default")
      (node (ref "U23") (pin "45") (pinfunction "IO4_0_45") (pintype "passive"))
    )
    (net (code "131") (name "/3_IO_4_1") (class "Default")
      (node (ref "U23") (pin "47") (pinfunction "IO4_1_47") (pintype "passive"))
    )
    (net (code "132") (name "/3_IO_4_2") (class "Default")
      (node (ref "U23") (pin "48") (pinfunction "IO4_2_48") (pintype "passive"))
    )
    (net (code "133") (name "/3_IO_4_3") (class "Default")
      (node (ref "U23") (pin "49") (pinfunction "IO4_3_49") (pintype "passive"))
    )
    (net (code "134") (name "/3_IO_4_4") (class "Default")
      (node (ref "U23") (pin "50") (pinfunction "IO4_4_50") (pintype "passive"))
    )
    (net (code "135") (name "/3_IO_4_5") (class "Default")
      (node (ref "U23") (pin "52") (pinfunction "IO4_5_52") (pintype "passive"))
    )
    (net (code "136") (name "/3_IO_4_6") (class "Default")
      (node (ref "U23") (pin "53") (pinfunction "IO4_6_53") (pintype "passive"))
    )
    (net (code "137") (name "/3_IO_4_7") (class "Default")
      (node (ref "U23") (pin "54") (pinfunction "IO4_7_54") (pintype "passive"))
    )
    (net (code "138") (name "/3_OE_PCA") (class "Default")
      (node (ref "R11") (pin "2") (pinfunction "2_2") (pintype "passive"))
      (node (ref "U23") (pin "30") (pinfunction "OE#_30") (pintype "passive"))
    )
    (net (code "139") (name "/3_RESET_PCA") (class "Default")
      (node (ref "R12") (pin "2") (pinfunction "2_2") (pintype "passive"))
      (node (ref "U23") (pin "56") (pinfunction "RESET#_56") (pintype "passive"))
    )
    (net (code "140") (name "/LED_IN") (class "Default")
      (node (ref "Q1") (pin "3") (pinfunction "D_3") (pintype "passive"))
      (node (ref "R16") (pin "1") (pinfunction "1_1") (pintype "passive"))
      (node (ref "SW0") (pin "DI") (pinfunction "DI_DI") (pintype "passive"))
    )
    (net (code "141") (name "/LED_OUT") (class "Default")
      (node (ref "SW102") (pin "DO") (pinfunction "DO_DO") (pintype "passive"))
    )
    (net (code "142") (name "/MCU_LED_OUT") (class "Default")
      (node (ref "H3") (pin "1") (pinfunction "1_1") (pintype "passive"))
      (node (ref "Q1") (pin "2") (pinfunction "S_2") (pintype "passive"))
      (node (ref "R17") (pin "1") (pinfunction "1_1") (pintype "passive"))
      (node (ref "U3") (pin "1") (pinfunction "P0.2_1") (pintype "passive"))
    )
    (net (code "143") (name "/POT_OUT") (class "Default")
      (node (ref "H3") (pin "2") (pinfunction "2_2") (pintype "passive"))
      (node (ref "H9") (pin "2") (pinfunction "2_2") (pintype "passive"))
      (node (ref "U3") (pin "2") (pinfunction "P0.3_2") (pintype "passive"))
    )
    (net (code "144") (name "/SCL_PCA") (class "Default")
      (node (ref "H3") (pin "6") (pinfunction "6_6") (pintype "passive"))
      (node (ref "R15") (pin "2") (pinfunction "2_2") (pintype "passive"))
      (node (ref "R2") (pin "2") (pinfunction "2_2") (pintype "passive"))
      (node (ref "R6") (pin "2") (pinfunction "2_2") (pintype "passive"))
      (node (ref "U1") (pin "2") (pinfunction "SCL_2") (pintype "passive"))
      (node (ref "U10") (pin "2") (pinfunction "SCL_2") (pintype "passive"))
      (node (ref "U23") (pin "2") (pinfunction "SCL_2") (pintype "passive"))
      (node (ref "U3") (pin "6") (pinfunction "P0.5_6") (pintype "passive"))
    )
    (net (code "145") (name "/SDA_PCA") (class "Default")
      (node (ref "H3") (pin "5") (pinfunction "5_5") (pintype "passive"))
      (node (ref "R1") (pin "2") (pinfunction "2_2") (pintype "passive"))
      (node (ref "R14") (pin "2") (pinfunction "2_2") (pintype "passive"))
      (node (ref "R7") (pin "2") (pinfunction "2_2") (pintype "passive"))
      (node (ref "U1") (pin "1") (pinfunction "SDA_1") (pintype "passive"))
      (node (ref "U10") (pin "1") (pinfunction "SDA_1") (pintype "passive"))
      (node (ref "U23") (pin "1") (pinfunction "SDA_1") (pintype "passive"))
      (node (ref "U3") (pin "5") (pinfunction "P0.4_5") (pintype "passive"))
    )
    (net (code "146") (name "/VDD_PCA") (class "Default")
      (node (ref "C1") (pin "1") (pinfunction "1_1") (pintype "passive"))
      (node (ref "C2") (pin "1") (pinfunction "1_1") (pintype "passive"))
      (node (ref "C3") (pin "1") (pinfunction "1_1") (pintype "passive"))
      (node (ref "C4") (pin "1") (pinfunction "1_1") (pintype "passive"))
      (node (ref "C5") (pin "1") (pinfunction "1_1") (pintype "passive"))
      (node (ref "C6") (pin "1") (pinfunction "1_1") (pintype "passive"))
      (node (ref "H1") (pin "7") (pinfunction "7_7") (pintype "passive"))
      (node (ref "H9") (pin "1") (pinfunction "1_1") (pintype "passive"))
      (node (ref "R1") (pin "1") (pinfunction "1_1") (pintype "passive"))
      (node (ref "R10") (pin "1") (pinfunction "1_1") (pintype "passive"))
      (node (ref "R11") (pin "1") (pinfunction "1_1") (pintype "passive"))
      (node (ref "R12") (pin "1") (pinfunction "1_1") (pintype "passive"))
      (node (ref "R13") (pin "1") (pinfunction "1_1") (pintype "passive"))
      (node (ref "R14") (pin "1") (pinfunction "1_1") (pintype "passive"))
      (node (ref "R15") (pin "1") (pinfunction "1_1") (pintype "passive"))
      (node (ref "R16") (pin "2") (pinfunction "2_2") (pintype "passive"))
      (node (ref "R2") (pin "1") (pinfunction "1_1") (pintype "passive"))
      (node (ref "R3") (pin "1") (pinfunction "1_1") (pintype "passive"))
      (node (ref "R4") (pin "1") (pinfunction "1_1") (pintype "passive"))
      (node (ref "R5") (pin "1") (pinfunction "1_1") (pintype "passive"))
      (node (ref "R6") (pin "1") (pinfunction "1_1") (pintype "passive"))
      (node (ref "R7") (pin "1") (pinfunction "1_1") (pintype "passive"))
      (node (ref "R8") (pin "1") (pinfunction "1_1") (pintype "passive"))
      (node (ref "R9") (pin "1") (pinfunction "1_1") (pintype "passive"))
      (node (ref "SW0") (pin "VCC") (pinfunction "VCC_VCC") (pintype "passive"))
      (node (ref "SW1") (pin "VCC") (pinfunction "VCC_VCC") (pintype "passive"))
      (node (ref "SW10") (pin "VCC") (pinfunction "VCC_VCC") (pintype "passive"))
      (node (ref "SW100") (pin "VCC") (pinfunction "VCC_VCC") (pintype "passive"))
      (node (ref "SW101") (pin "VCC") (pinfunction "VCC_VCC") (pintype "passive"))
      (node (ref "SW102") (pin "VCC") (pinfunction "VCC_VCC") (pintype "passive"))
      (node (ref "SW104") (pin "VCC") (pinfunction "VCC_VCC") (pintype "passive"))
      (node (ref "SW11") (pin "VCC") (pinfunction "VCC_VCC") (pintype "passive"))
      (node (ref "SW12") (pin "VCC") (pinfunction "VCC_VCC") (pintype "passive"))
      (node (ref "SW13") (pin "VCC") (pinfunction "VCC_VCC") (pintype "passive"))
      (node (ref "SW14") (pin "VCC") (pinfunction "VCC_VCC") (pintype "passive"))
      (node (ref "SW15") (pin "VCC") (pinfunction "VCC_VCC") (pintype "passive"))
      (node (ref "SW16") (pin "VCC") (pinfunction "VCC_VCC") (pintype "passive"))
      (node (ref "SW17") (pin "VCC") (pinfunction "VCC_VCC") (pintype "passive"))
      (node (ref "SW18") (pin "VCC") (pinfunction "VCC_VCC") (pintype "passive"))
      (node (ref "SW19") (pin "VCC") (pinfunction "VCC_VCC") (pintype "passive"))
      (node (ref "SW2") (pin "VCC") (pinfunction "VCC_VCC") (pintype "passive"))
      (node (ref "SW20") (pin "VCC") (pinfunction "VCC_VCC") (pintype "passive"))
      (node (ref "SW21") (pin "VCC") (pinfunction "VCC_VCC") (pintype "passive"))
      (node (ref "SW22") (pin "VCC") (pinfunction "VCC_VCC") (pintype "passive"))
      (node (ref "SW23") (pin "VCC") (pinfunction "VCC_VCC") (pintype "passive"))
      (node (ref "SW24") (pin "VCC") (pinfunction "VCC_VCC") (pintype "passive"))
      (node (ref "SW25") (pin "VCC") (pinfunction "VCC_VCC") (pintype "passive"))
      (node (ref "SW26") (pin "VCC") (pinfunction "VCC_VCC") (pintype "passive"))
      (node (ref "SW28") (pin "VCC") (pinfunction "VCC_VCC") (pintype "passive"))
      (node (ref "SW29") (pin "VCC") (pinfunction "VCC_VCC") (pintype "passive"))
      (node (ref "SW3") (pin "VCC") (pinfunction "VCC_VCC") (pintype "passive"))
      (node (ref "SW31") (pin "VCC") (pinfunction "VCC_VCC") (pintype "passive"))
      (node (ref "SW32") (pin "VCC") (pinfunction "VCC_VCC") (pintype "passive"))
      (node (ref "SW33") (pin "VCC") (pinfunction "VCC_VCC") (pintype "passive"))
      (node (ref "SW34") (pin "VCC") (pinfunction "VCC_VCC") (pintype "passive"))
      (node (ref "SW35") (pin "VCC") (pinfunction "VCC_VCC") (pintype "passive"))
      (node (ref "SW36") (pin "VCC") (pinfunction "VCC_VCC") (pintype "passive"))
      (node (ref "SW37") (pin "VCC") (pinfunction "VCC_VCC") (pintype "passive"))
      (node (ref "SW38") (pin "VCC") (pinfunction "VCC_VCC") (pintype "passive"))
      (node (ref "SW4") (pin "VCC") (pinfunction "VCC_VCC") (pintype "passive"))
      (node (ref "SW40") (pin "VCC") (pinfunction "VCC_VCC") (pintype "passive"))
      (node (ref "SW41") (pin "VCC") (pinfunction "VCC_VCC") (pintype "passive"))
      (node (ref "SW42") (pin "VCC") (pinfunction "VCC_VCC") (pintype "passive"))
      (node (ref "SW43") (pin "VCC") (pinfunction "VCC_VCC") (pintype "passive"))
      (node (ref "SW44") (pin "VCC") (pinfunction "VCC_VCC") (pintype "passive"))
      (node (ref "SW45") (pin "VCC") (pinfunction "VCC_VCC") (pintype "passive"))
      (node (ref "SW46") (pin "VCC") (pinfunction "VCC_VCC") (pintype "passive"))
      (node (ref "SW47") (pin "VCC") (pinfunction "VCC_VCC") (pintype "passive"))
      (node (ref "SW48") (pin "VCC") (pinfunction "VCC_VCC") (pintype "passive"))
      (node (ref "SW49") (pin "VCC") (pinfunction "VCC_VCC") (pintype "passive"))
      (node (ref "SW5") (pin "VCC") (pinfunction "VCC_VCC") (pintype "passive"))
      (node (ref "SW50") (pin "VCC") (pinfunction "VCC_VCC") (pintype "passive"))
      (node (ref "SW52") (pin "VCC") (pinfunction "VCC_VCC") (pintype "passive"))
      (node (ref "SW53") (pin "VCC") (pinfunction "VCC_VCC") (pintype "passive"))
      (node (ref "SW55") (pin "VCC") (pinfunction "VCC_VCC") (pintype "passive"))
      (node (ref "SW56") (pin "VCC") (pinfunction "VCC_VCC") (pintype "passive"))
      (node (ref "SW57") (pin "VCC") (pinfunction "VCC_VCC") (pintype "passive"))
      (node (ref "SW58") (pin "VCC") (pinfunction "VCC_VCC") (pintype "passive"))
      (node (ref "SW59") (pin "VCC") (pinfunction "VCC_VCC") (pintype "passive"))
      (node (ref "SW6") (pin "VCC") (pinfunction "VCC_VCC") (pintype "passive"))
      (node (ref "SW60") (pin "VCC") (pinfunction "VCC_VCC") (pintype "passive"))
      (node (ref "SW61") (pin "VCC") (pinfunction "VCC_VCC") (pintype "passive"))
      (node (ref "SW62") (pin "VCC") (pinfunction "VCC_VCC") (pintype "passive"))
      (node (ref "SW64") (pin "VCC") (pinfunction "VCC_VCC") (pintype "passive"))
      (node (ref "SW65") (pin "VCC") (pinfunction "VCC_VCC") (pintype "passive"))
      (node (ref "SW66") (pin "VCC") (pinfunction "VCC_VCC") (pintype "passive"))
      (node (ref "SW67") (pin "VCC") (pinfunction "VCC_VCC") (pintype "passive"))
      (node (ref "SW68") (pin "VCC") (pinfunction "VCC_VCC") (pintype "passive"))
      (node (ref "SW69") (pin "VCC") (pinfunction "VCC_VCC") (pintype "passive"))
      (node (ref "SW7") (pin "VCC") (pinfunction "VCC_VCC") (pintype "passive"))
      (node (ref "SW70") (pin "VCC") (pinfunction "VCC_VCC") (pintype "passive"))
      (node (ref "SW71") (pin "VCC") (pinfunction "VCC_VCC") (pintype "passive"))
      (node (ref "SW72") (pin "VCC") (pinfunction "VCC_VCC") (pintype "passive"))
      (node (ref "SW73") (pin "VCC") (pinfunction "VCC_VCC") (pintype "passive"))
      (node (ref "SW74") (pin "VCC") (pinfunction "VCC_VCC") (pintype "passive"))
      (node (ref "SW75") (pin "VCC") (pinfunction "VCC_VCC") (pintype "passive"))
      (node (ref "SW76") (pin "VCC") (pinfunction "VCC_VCC") (pintype "passive"))
      (node (ref "SW78") (pin "VCC") (pinfunction "VCC_VCC") (pintype "passive"))
      (node (ref "SW8") (pin "VCC") (pinfunction "VCC_VCC") (pintype "passive"))
      (node (ref "SW80") (pin "VCC") (pinfunction "VCC_VCC") (pintype "passive"))
      (node (ref "SW81") (pin "VCC") (pinfunction "VCC_VCC") (pintype "passive"))
      (node (ref "SW82") (pin "VCC") (pinfunction "VCC_VCC") (pintype "passive"))
      (node (ref "SW83") (pin "VCC") (pinfunction "VCC_VCC") (pintype "passive"))
      (node (ref "SW84") (pin "VCC") (pinfunction "VCC_VCC") (pintype "passive"))
      (node (ref "SW85") (pin "VCC") (pinfunction "VCC_VCC") (pintype "passive"))
      (node (ref "SW86") (pin "VCC") (pinfunction "VCC_VCC") (pintype "passive"))
      (node (ref "SW87") (pin "VCC") (pinfunction "VCC_VCC") (pintype "passive"))
      (node (ref "SW88") (pin "VCC") (pinfunction "VCC_VCC") (pintype "passive"))
      (node (ref "SW89") (pin "VCC") (pinfunction "VCC_VCC") (pintype "passive"))
      (node (ref "SW9") (pin "VCC") (pinfunction "VCC_VCC") (pintype "passive"))
      (node (ref "SW91") (pin "VCC") (pinfunction "VCC_VCC") (pintype "passive"))
      (node (ref "SW92") (pin "VCC") (pinfunction "VCC_VCC") (pintype "passive"))
      (node (ref "SW93") (pin "VCC") (pinfunction "VCC_VCC") (pintype "passive"))
      (node (ref "SW94") (pin "VCC") (pinfunction "VCC_VCC") (pintype "passive"))
      (node (ref "SW95") (pin "VCC") (pinfunction "VCC_VCC") (pintype "passive"))
      (node (ref "SW96") (pin "VCC") (pinfunction "VCC_VCC") (pintype "passive"))
      (node (ref "SW97") (pin "VCC") (pinfunction "VCC_VCC") (pintype "passive"))
      (node (ref "SW98") (pin "VCC") (pinfunction "VCC_VCC") (pintype "passive"))
      (node (ref "SW99") (pin "VCC") (pinfunction "VCC_VCC") (pintype "passive"))
      (node (ref "U1") (pin "18") (pinfunction "VDD_18") (pintype "passive"))
      (node (ref "U1") (pin "46") (pinfunction "VDD_46") (pintype "passive"))
      (node (ref "U10") (pin "18") (pinfunction "VDD_18") (pintype "passive"))
      (node (ref "U10") (pin "46") (pinfunction "VDD_46") (pintype "passive"))
      (node (ref "U11") (pin "2") (pinfunction "2_2") (pintype "passive"))
      (node (ref "U14") (pin "2") (pinfunction "2_2") (pintype "passive"))
      (node (ref "U15") (pin "2") (pinfunction "2_2") (pintype "passive"))
      (node (ref "U18") (pin "2") (pinfunction "2_2") (pintype "passive"))
      (node (ref "U19") (pin "2") (pinfunction "2_2") (pintype "passive"))
      (node (ref "U22") (pin "2") (pinfunction "2_2") (pintype "passive"))
      (node (ref "U23") (pin "18") (pinfunction "VDD_18") (pintype "passive"))
      (node (ref "U23") (pin "46") (pinfunction "VDD_46") (pintype "passive"))
      (node (ref "U3") (pin "14") (pinfunction "5V_14") (pintype "passive"))
      (node (ref "U5") (pin "2") (pinfunction "2_2") (pintype "passive"))
      (node (ref "U6") (pin "2") (pinfunction "2_2") (pintype "passive"))
      (node (ref "U9") (pin "2") (pinfunction "2_2") (pintype "passive"))
    )
    (net (code "147") (name "GND") (class "Default")
      (node (ref "C1") (pin "2") (pinfunction "2_2") (pintype "passive"))
      (node (ref "C2") (pin "2") (pinfunction "2_2") (pintype "passive"))
      (node (ref "C3") (pin "2") (pinfunction "2_2") (pintype "passive"))
      (node (ref "C4") (pin "2") (pinfunction "2_2") (pintype "passive"))
      (node (ref "C5") (pin "2") (pinfunction "2_2") (pintype "passive"))
      (node (ref "C6") (pin "2") (pinfunction "2_2") (pintype "passive"))
      (node (ref "H1") (pin "6") (pinfunction "6_6") (pintype "passive"))
      (node (ref "H9") (pin "3") (pinfunction "3_3") (pintype "passive"))
      (node (ref "SW0") (pin "GND") (pinfunction "GND_GND") (pintype "passive"))
      (node (ref "SW0") (pin "SW2") (pinfunction "SW2_SW2") (pintype "passive"))
      (node (ref "SW1") (pin "GND") (pinfunction "GND_GND") (pintype "passive"))
      (node (ref "SW1") (pin "SW2") (pinfunction "SW2_SW2") (pintype "passive"))
      (node (ref "SW10") (pin "GND") (pinfunction "GND_GND") (pintype "passive"))
      (node (ref "SW10") (pin "SW2") (pinfunction "SW2_SW2") (pintype "passive"))
      (node (ref "SW100") (pin "GND") (pinfunction "GND_GND") (pintype "passive"))
      (node (ref "SW100") (pin "SW2") (pinfunction "SW2_SW2") (pintype "passive"))
      (node (ref "SW101") (pin "GND") (pinfunction "GND_GND") (pintype "passive"))
      (node (ref "SW101") (pin "SW2") (pinfunction "SW2_SW2") (pintype "passive"))
      (node (ref "SW102") (pin "GND") (pinfunction "GND_GND") (pintype "passive"))
      (node (ref "SW102") (pin "SW2") (pinfunction "SW2_SW2") (pintype "passive"))
      (node (ref "SW104") (pin "GND") (pinfunction "GND_GND") (pintype "passive"))
      (node (ref "SW104") (pin "SW2") (pinfunction "SW2_SW2") (pintype "passive"))
      (node (ref "SW11") (pin "GND") (pinfunction "GND_GND") (pintype "passive"))
      (node (ref "SW11") (pin "SW2") (pinfunction "SW2_SW2") (pintype "passive"))
      (node (ref "SW12") (pin "GND") (pinfunction "GND_GND") (pintype "passive"))
      (node (ref "SW12") (pin "SW2") (pinfunction "SW2_SW2") (pintype "passive"))
      (node (ref "SW13") (pin "GND") (pinfunction "GND_GND") (pintype "passive"))
      (node (ref "SW13") (pin "SW2") (pinfunction "SW2_SW2") (pintype "passive"))
      (node (ref "SW14") (pin "GND") (pinfunction "GND_GND") (pintype "passive"))
      (node (ref "SW14") (pin "SW2") (pinfunction "SW2_SW2") (pintype "passive"))
      (node (ref "SW15") (pin "GND") (pinfunction "GND_GND") (pintype "passive"))
      (node (ref "SW15") (pin "SW2") (pinfunction "SW2_SW2") (pintype "passive"))
      (node (ref "SW16") (pin "GND") (pinfunction "GND_GND") (pintype "passive"))
      (node (ref "SW16") (pin "SW2") (pinfunction "SW2_SW2") (pintype "passive"))
      (node (ref "SW17") (pin "GND") (pinfunction "GND_GND") (pintype "passive"))
      (node (ref "SW17") (pin "SW2") (pinfunction "SW2_SW2") (pintype "passive"))
      (node (ref "SW18") (pin "GND") (pinfunction "GND_GND") (pintype "passive"))
      (node (ref "SW18") (pin "SW2") (pinfunction "SW2_SW2") (pintype "passive"))
      (node (ref "SW19") (pin "GND") (pinfunction "GND_GND") (pintype "passive"))
      (node (ref "SW19") (pin "SW2") (pinfunction "SW2_SW2") (pintype "passive"))
      (node (ref "SW2") (pin "GND") (pinfunction "GND_GND") (pintype "passive"))
      (node (ref "SW2") (pin "SW2") (pinfunction "SW2_SW2") (pintype "passive"))
      (node (ref "SW20") (pin "GND") (pinfunction "GND_GND") (pintype "passive"))
      (node (ref "SW20") (pin "SW2") (pinfunction "SW2_SW2") (pintype "passive"))
      (node (ref "SW21") (pin "GND") (pinfunction "GND_GND") (pintype "passive"))
      (node (ref "SW21") (pin "SW2") (pinfunction "SW2_SW2") (pintype "passive"))
      (node (ref "SW22") (pin "GND") (pinfunction "GND_GND") (pintype "passive"))
      (node (ref "SW22") (pin "SW2") (pinfunction "SW2_SW2") (pintype "passive"))
      (node (ref "SW23") (pin "GND") (pinfunction "GND_GND") (pintype "passive"))
      (node (ref "SW23") (pin "SW2") (pinfunction "SW2_SW2") (pintype "passive"))
      (node (ref "SW24") (pin "GND") (pinfunction "GND_GND") (pintype "passive"))
      (node (ref "SW24") (pin "SW2") (pinfunction "SW2_SW2") (pintype "passive"))
      (node (ref "SW25") (pin "GND") (pinfunction "GND_GND") (pintype "passive"))
      (node (ref "SW25") (pin "SW2") (pinfunction "SW2_SW2") (pintype "passive"))
      (node (ref "SW26") (pin "GND") (pinfunction "GND_GND") (pintype "passive"))
      (node (ref "SW26") (pin "SW2") (pinfunction "SW2_SW2") (pintype "passive"))
      (node (ref "SW28") (pin "GND") (pinfunction "GND_GND") (pintype "passive"))
      (node (ref "SW28") (pin "SW2") (pinfunction "SW2_SW2") (pintype "passive"))
      (node (ref "SW29") (pin "GND") (pinfunction "GND_GND") (pintype "passive"))
      (node (ref "SW29") (pin "SW2") (pinfunction "SW2_SW2") (pintype "passive"))
      (node (ref "SW3") (pin "GND") (pinfunction "GND_GND") (pintype "passive"))
      (node (ref "SW3") (pin "SW2") (pinfunction "SW2_SW2") (pintype "passive"))
      (node (ref "SW31") (pin "GND") (pinfunction "GND_GND") (pintype "passive"))
      (node (ref "SW31") (pin "SW2") (pinfunction "SW2_SW2") (pintype "passive"))
      (node (ref "SW32") (pin "GND") (pinfunction "GND_GND") (pintype "passive"))
      (node (ref "SW32") (pin "SW2") (pinfunction "SW2_SW2") (pintype "passive"))
      (node (ref "SW33") (pin "GND") (pinfunction "GND_GND") (pintype "passive"))
      (node (ref "SW33") (pin "SW2") (pinfunction "SW2_SW2") (pintype "passive"))
      (node (ref "SW34") (pin "GND") (pinfunction "GND_GND") (pintype "passive"))
      (node (ref "SW34") (pin "SW2") (pinfunction "SW2_SW2") (pintype "passive"))
      (node (ref "SW35") (pin "GND") (pinfunction "GND_GND") (pintype "passive"))
      (node (ref "SW35") (pin "SW2") (pinfunction "SW2_SW2") (pintype "passive"))
      (node (ref "SW36") (pin "GND") (pinfunction "GND_GND") (pintype "passive"))
      (node (ref "SW36") (pin "SW2") (pinfunction "SW2_SW2") (pintype "passive"))
      (node (ref "SW37") (pin "GND") (pinfunction "GND_GND") (pintype "passive"))
      (node (ref "SW37") (pin "SW2") (pinfunction "SW2_SW2") (pintype "passive"))
      (node (ref "SW38") (pin "GND") (pinfunction "GND_GND") (pintype "passive"))
      (node (ref "SW38") (pin "SW2") (pinfunction "SW2_SW2") (pintype "passive"))
      (node (ref "SW4") (pin "GND") (pinfunction "GND_GND") (pintype "passive"))
      (node (ref "SW4") (pin "SW2") (pinfunction "SW2_SW2") (pintype "passive"))
      (node (ref "SW40") (pin "GND") (pinfunction "GND_GND") (pintype "passive"))
      (node (ref "SW40") (pin "SW2") (pinfunction "SW2_SW2") (pintype "passive"))
      (node (ref "SW41") (pin "GND") (pinfunction "GND_GND") (pintype "passive"))
      (node (ref "SW41") (pin "SW2") (pinfunction "SW2_SW2") (pintype "passive"))
      (node (ref "SW42") (pin "GND") (pinfunction "GND_GND") (pintype "passive"))
      (node (ref "SW42") (pin "SW2") (pinfunction "SW2_SW2") (pintype "passive"))
      (node (ref "SW43") (pin "GND") (pinfunction "GND_GND") (pintype "passive"))
      (node (ref "SW43") (pin "SW2") (pinfunction "SW2_SW2") (pintype "passive"))
      (node (ref "SW44") (pin "GND") (pinfunction "GND_GND") (pintype "passive"))
      (node (ref "SW44") (pin "SW2") (pinfunction "SW2_SW2") (pintype "passive"))
      (node (ref "SW45") (pin "GND") (pinfunction "GND_GND") (pintype "passive"))
      (node (ref "SW45") (pin "SW2") (pinfunction "SW2_SW2") (pintype "passive"))
      (node (ref "SW46") (pin "GND") (pinfunction "GND_GND") (pintype "passive"))
      (node (ref "SW46") (pin "SW2") (pinfunction "SW2_SW2") (pintype "passive"))
      (node (ref "SW47") (pin "GND") (pinfunction "GND_GND") (pintype "passive"))
      (node (ref "SW47") (pin "SW2") (pinfunction "SW2_SW2") (pintype "passive"))
      (node (ref "SW48") (pin "GND") (pinfunction "GND_GND") (pintype "passive"))
      (node (ref "SW48") (pin "SW2") (pinfunction "SW2_SW2") (pintype "passive"))
      (node (ref "SW49") (pin "GND") (pinfunction "GND_GND") (pintype "passive"))
      (node (ref "SW49") (pin "SW2") (pinfunction "SW2_SW2") (pintype "passive"))
      (node (ref "SW5") (pin "GND") (pinfunction "GND_GND") (pintype "passive"))
      (node (ref "SW5") (pin "SW2") (pinfunction "SW2_SW2") (pintype "passive"))
      (node (ref "SW50") (pin "GND") (pinfunction "GND_GND") (pintype "passive"))
      (node (ref "SW50") (pin "SW2") (pinfunction "SW2_SW2") (pintype "passive"))
      (node (ref "SW52") (pin "GND") (pinfunction "GND_GND") (pintype "passive"))
      (node (ref "SW52") (pin "SW2") (pinfunction "SW2_SW2") (pintype "passive"))
      (node (ref "SW53") (pin "GND") (pinfunction "GND_GND") (pintype "passive"))
      (node (ref "SW53") (pin "SW2") (pinfunction "SW2_SW2") (pintype "passive"))
      (node (ref "SW55") (pin "GND") (pinfunction "GND_GND") (pintype "passive"))
      (node (ref "SW55") (pin "SW2") (pinfunction "SW2_SW2") (pintype "passive"))
      (node (ref "SW56") (pin "GND") (pinfunction "GND_GND") (pintype "passive"))
      (node (ref "SW56") (pin "SW2") (pinfunction "SW2_SW2") (pintype "passive"))
      (node (ref "SW57") (pin "GND") (pinfunction "GND_GND") (pintype "passive"))
      (node (ref "SW57") (pin "SW2") (pinfunction "SW2_SW2") (pintype "passive"))
      (node (ref "SW58") (pin "GND") (pinfunction "GND_GND") (pintype "passive"))
      (node (ref "SW58") (pin "SW2") (pinfunction "SW2_SW2") (pintype "passive"))
      (node (ref "SW59") (pin "GND") (pinfunction "GND_GND") (pintype "passive"))
      (node (ref "SW59") (pin "SW2") (pinfunction "SW2_SW2") (pintype "passive"))
      (node (ref "SW6") (pin "GND") (pinfunction "GND_GND") (pintype "passive"))
      (node (ref "SW6") (pin "SW2") (pinfunction "SW2_SW2") (pintype "passive"))
      (node (ref "SW60") (pin "GND") (pinfunction "GND_GND") (pintype "passive"))
      (node (ref "SW60") (pin "SW2") (pinfunction "SW2_SW2") (pintype "passive"))
      (node (ref "SW61") (pin "GND") (pinfunction "GND_GND") (pintype "passive"))
      (node (ref "SW61") (pin "SW2") (pinfunction "SW2_SW2") (pintype "passive"))
      (node (ref "SW62") (pin "GND") (pinfunction "GND_GND") (pintype "passive"))
      (node (ref "SW62") (pin "SW2") (pinfunction "SW2_SW2") (pintype "passive"))
      (node (ref "SW64") (pin "GND") (pinfunction "GND_GND") (pintype "passive"))
      (node (ref "SW64") (pin "SW2") (pinfunction "SW2_SW2") (pintype "passive"))
      (node (ref "SW65") (pin "GND") (pinfunction "GND_GND") (pintype "passive"))
      (node (ref "SW65") (pin "SW2") (pinfunction "SW2_SW2") (pintype "passive"))
      (node (ref "SW66") (pin "GND") (pinfunction "GND_GND") (pintype "passive"))
      (node (ref "SW66") (pin "SW2") (pinfunction "SW2_SW2") (pintype "passive"))
      (node (ref "SW67") (pin "GND") (pinfunction "GND_GND") (pintype "passive"))
      (node (ref "SW67") (pin "SW2") (pinfunction "SW2_SW2") (pintype "passive"))
      (node (ref "SW68") (pin "GND") (pinfunction "GND_GND") (pintype "passive"))
      (node (ref "SW68") (pin "SW2") (pinfunction "SW2_SW2") (pintype "passive"))
      (node (ref "SW69") (pin "GND") (pinfunction "GND_GND") (pintype "passive"))
      (node (ref "SW69") (pin "SW2") (pinfunction "SW2_SW2") (pintype "passive"))
      (node (ref "SW7") (pin "GND") (pinfunction "GND_GND") (pintype "passive"))
      (node (ref "SW7") (pin "SW2") (pinfunction "SW2_SW2") (pintype "passive"))
      (node (ref "SW70") (pin "GND") (pinfunction "GND_GND") (pintype "passive"))
      (node (ref "SW70") (pin "SW2") (pinfunction "SW2_SW2") (pintype "passive"))
      (node (ref "SW71") (pin "GND") (pinfunction "GND_GND") (pintype "passive"))
      (node (ref "SW71") (pin "SW2") (pinfunction "SW2_SW2") (pintype "passive"))
      (node (ref "SW72") (pin "GND") (pinfunction "GND_GND") (pintype "passive"))
      (node (ref "SW72") (pin "SW2") (pinfunction "SW2_SW2") (pintype "passive"))
      (node (ref "SW73") (pin "GND") (pinfunction "GND_GND") (pintype "passive"))
      (node (ref "SW73") (pin "SW2") (pinfunction "SW2_SW2") (pintype "passive"))
      (node (ref "SW74") (pin "GND") (pinfunction "GND_GND") (pintype "passive"))
      (node (ref "SW74") (pin "SW2") (pinfunction "SW2_SW2") (pintype "passive"))
      (node (ref "SW75") (pin "GND") (pinfunction "GND_GND") (pintype "passive"))
      (node (ref "SW75") (pin "SW2") (pinfunction "SW2_SW2") (pintype "passive"))
      (node (ref "SW76") (pin "GND") (pinfunction "GND_GND") (pintype "passive"))
      (node (ref "SW76") (pin "SW2") (pinfunction "SW2_SW2") (pintype "passive"))
      (node (ref "SW78") (pin "GND") (pinfunction "GND_GND") (pintype "passive"))
      (node (ref "SW78") (pin "SW2") (pinfunction "SW2_SW2") (pintype "passive"))
      (node (ref "SW8") (pin "GND") (pinfunction "GND_GND") (pintype "passive"))
      (node (ref "SW8") (pin "SW2") (pinfunction "SW2_SW2") (pintype "passive"))
      (node (ref "SW80") (pin "GND") (pinfunction "GND_GND") (pintype "passive"))
      (node (ref "SW80") (pin "SW2") (pinfunction "SW2_SW2") (pintype "passive"))
      (node (ref "SW81") (pin "GND") (pinfunction "GND_GND") (pintype "passive"))
      (node (ref "SW81") (pin "SW2") (pinfunction "SW2_SW2") (pintype "passive"))
      (node (ref "SW82") (pin "GND") (pinfunction "GND_GND") (pintype "passive"))
      (node (ref "SW82") (pin "SW2") (pinfunction "SW2_SW2") (pintype "passive"))
      (node (ref "SW83") (pin "GND") (pinfunction "GND_GND") (pintype "passive"))
      (node (ref "SW83") (pin "SW2") (pinfunction "SW2_SW2") (pintype "passive"))
      (node (ref "SW84") (pin "GND") (pinfunction "GND_GND") (pintype "passive"))
      (node (ref "SW84") (pin "SW2") (pinfunction "SW2_SW2") (pintype "passive"))
      (node (ref "SW85") (pin "GND") (pinfunction "GND_GND") (pintype "passive"))
      (node (ref "SW85") (pin "SW2") (pinfunction "SW2_SW2") (pintype "passive"))
      (node (ref "SW86") (pin "GND") (pinfunction "GND_GND") (pintype "passive"))
      (node (ref "SW86") (pin "SW2") (pinfunction "SW2_SW2") (pintype "passive"))
      (node (ref "SW87") (pin "GND") (pinfunction "GND_GND") (pintype "passive"))
      (node (ref "SW87") (pin "SW2") (pinfunction "SW2_SW2") (pintype "passive"))
      (node (ref "SW88") (pin "GND") (pinfunction "GND_GND") (pintype "passive"))
      (node (ref "SW88") (pin "SW2") (pinfunction "SW2_SW2") (pintype "passive"))
      (node (ref "SW89") (pin "GND") (pinfunction "GND_GND") (pintype "passive"))
      (node (ref "SW89") (pin "SW2") (pinfunction "SW2_SW2") (pintype "passive"))
      (node (ref "SW9") (pin "GND") (pinfunction "GND_GND") (pintype "passive"))
      (node (ref "SW9") (pin "SW2") (pinfunction "SW2_SW2") (pintype "passive"))
      (node (ref "SW91") (pin "GND") (pinfunction "GND_GND") (pintype "passive"))
      (node (ref "SW91") (pin "SW2") (pinfunction "SW2_SW2") (pintype "passive"))
      (node (ref "SW92") (pin "GND") (pinfunction "GND_GND") (pintype "passive"))
      (node (ref "SW92") (pin "SW2") (pinfunction "SW2_SW2") (pintype "passive"))
      (node (ref "SW93") (pin "GND") (pinfunction "GND_GND") (pintype "passive"))
      (node (ref "SW93") (pin "SW2") (pinfunction "SW2_SW2") (pintype "passive"))
      (node (ref "SW94") (pin "GND") (pinfunction "GND_GND") (pintype "passive"))
      (node (ref "SW94") (pin "SW2") (pinfunction "SW2_SW2") (pintype "passive"))
      (node (ref "SW95") (pin "GND") (pinfunction "GND_GND") (pintype "passive"))
      (node (ref "SW95") (pin "SW2") (pinfunction "SW2_SW2") (pintype "passive"))
      (node (ref "SW96") (pin "GND") (pinfunction "GND_GND") (pintype "passive"))
      (node (ref "SW96") (pin "SW2") (pinfunction "SW2_SW2") (pintype "passive"))
      (node (ref "SW97") (pin "GND") (pinfunction "GND_GND") (pintype "passive"))
      (node (ref "SW97") (pin "SW2") (pinfunction "SW2_SW2") (pintype "passive"))
      (node (ref "SW98") (pin "GND") (pinfunction "GND_GND") (pintype "passive"))
      (node (ref "SW98") (pin "SW2") (pinfunction "SW2_SW2") (pintype "passive"))
      (node (ref "SW99") (pin "GND") (pinfunction "GND_GND") (pintype "passive"))
      (node (ref "SW99") (pin "SW2") (pinfunction "SW2_SW2") (pintype "passive"))
      (node (ref "U1") (pin "11") (pinfunction "VSS_11") (pintype "passive"))
      (node (ref "U1") (pin "23") (pinfunction "VSS_23") (pintype "passive"))
      (node (ref "U1") (pin "34") (pinfunction "VSS_34") (pintype "passive"))
      (node (ref "U1") (pin "39") (pinfunction "VSS_39") (pintype "passive"))
      (node (ref "U1") (pin "51") (pinfunction "VSS_51") (pintype "passive"))
      (node (ref "U1") (pin "6") (pinfunction "VSS_6") (pintype "passive"))
      (node (ref "U10") (pin "11") (pinfunction "VSS_11") (pintype "passive"))
      (node (ref "U10") (pin "23") (pinfunction "VSS_23") (pintype "passive"))
      (node (ref "U10") (pin "34") (pinfunction "VSS_34") (pintype "passive"))
      (node (ref "U10") (pin "39") (pinfunction "VSS_39") (pintype "passive"))
      (node (ref "U10") (pin "51") (pinfunction "VSS_51") (pintype "passive"))
      (node (ref "U10") (pin "6") (pinfunction "VSS_6") (pintype "passive"))
      (node (ref "U12") (pin "2") (pinfunction "2_2") (pintype "passive"))
      (node (ref "U13") (pin "2") (pinfunction "2_2") (pintype "passive"))
      (node (ref "U16") (pin "2") (pinfunction "2_2") (pintype "passive"))
      (node (ref "U17") (pin "2") (pinfunction "2_2") (pintype "passive"))
      (node (ref "U20") (pin "2") (pinfunction "2_2") (pintype "passive"))
      (node (ref "U21") (pin "2") (pinfunction "2_2") (pintype "passive"))
      (node (ref "U23") (pin "11") (pinfunction "VSS_11") (pintype "passive"))
      (node (ref "U23") (pin "23") (pinfunction "VSS_23") (pintype "passive"))
      (node (ref "U23") (pin "34") (pinfunction "VSS_34") (pintype "passive"))
      (node (ref "U23") (pin "39") (pinfunction "VSS_39") (pintype "passive"))
      (node (ref "U23") (pin "51") (pinfunction "VSS_51") (pintype "passive"))
      (node (ref "U23") (pin "6") (pinfunction "VSS_6") (pintype "passive"))
      (node (ref "U3") (pin "13") (pinfunction "GND_13") (pintype "passive"))
      (node (ref "U3") (pin "22") (pinfunction "GND_22") (pintype "passive"))
      (node (ref "U4") (pin "2") (pinfunction "2_2") (pintype "passive"))
      (node (ref "U7") (pin "2") (pinfunction "2_2") (pintype "passive"))
      (node (ref "U8") (pin "2") (pinfunction "2_2") (pintype "passive"))
    )
    (net (code "148") (name "Net-(SW0-PadDO)") (class "Default")
      (node (ref "SW0") (pin "DO") (pinfunction "DO_DO") (pintype "passive"))
      (node (ref "SW1") (pin "DI") (pinfunction "DI_DI") (pintype "passive"))
    )
    (net (code "149") (name "Net-(SW1-PadDO)") (class "Default")
      (node (ref "SW1") (pin "DO") (pinfunction "DO_DO") (pintype "passive"))
      (node (ref "SW2") (pin "DI") (pinfunction "DI_DI") (pintype "passive"))
    )
    (net (code "150") (name "Net-(SW2-PadDO)") (class "Default")
      (node (ref "SW2") (pin "DO") (pinfunction "DO_DO") (pintype "passive"))
      (node (ref "SW3") (pin "DI") (pinfunction "DI_DI") (pintype "passive"))
    )
    (net (code "151") (name "Net-(SW3-PadDO)") (class "Default")
      (node (ref "SW3") (pin "DO") (pinfunction "DO_DO") (pintype "passive"))
      (node (ref "SW4") (pin "DI") (pinfunction "DI_DI") (pintype "passive"))
    )
    (net (code "152") (name "Net-(SW4-PadDO)") (class "Default")
      (node (ref "SW4") (pin "DO") (pinfunction "DO_DO") (pintype "passive"))
      (node (ref "SW5") (pin "DI") (pinfunction "DI_DI") (pintype "passive"))
    )
    (net (code "153") (name "Net-(SW6-PadDI)") (class "Default")
      (node (ref "SW6") (pin "DI") (pinfunction "DI_DI") (pintype "passive"))
      (node (ref "SW9") (pin "DO") (pinfunction "DO_DO") (pintype "passive"))
    )
    (net (code "154") (name "Net-(SW6-PadDO)") (class "Default")
      (node (ref "SW6") (pin "DO") (pinfunction "DO_DO") (pintype "passive"))
      (node (ref "SW7") (pin "DI") (pinfunction "DI_DI") (pintype "passive"))
    )
    (net (code "155") (name "Net-(SW8-PadDO)") (class "Default")
      (node (ref "SW8") (pin "DO") (pinfunction "DO_DO") (pintype "passive"))
      (node (ref "SW9") (pin "DI") (pinfunction "DI_DI") (pintype "passive"))
    )
    (net (code "156") (name "Net-(SW10-PadDI)") (class "Default")
      (node (ref "SW10") (pin "DI") (pinfunction "DI_DI") (pintype "passive"))
      (node (ref "SW5") (pin "DO") (pinfunction "DO_DO") (pintype "passive"))
    )
    (net (code "157") (name "Net-(SW10-PadDO)") (class "Default")
      (node (ref "SW10") (pin "DO") (pinfunction "DO_DO") (pintype "passive"))
      (node (ref "SW8") (pin "DI") (pinfunction "DI_DI") (pintype "passive"))
    )
    (net (code "158") (name "Net-(SW11-PadDI)") (class "Default")
      (node (ref "SW11") (pin "DI") (pinfunction "DI_DI") (pintype "passive"))
      (node (ref "SW16") (pin "DO") (pinfunction "DO_DO") (pintype "passive"))
    )
    (net (code "159") (name "Net-(SW11-PadDO)") (class "Default")
      (node (ref "SW11") (pin "DO") (pinfunction "DO_DO") (pintype "passive"))
      (node (ref "SW24") (pin "DI") (pinfunction "DI_DI") (pintype "passive"))
    )
    (net (code "160") (name "Net-(SW12-PadDI)") (class "Default")
      (node (ref "SW12") (pin "DI") (pinfunction "DI_DI") (pintype "passive"))
      (node (ref "SW19") (pin "DO") (pinfunction "DO_DO") (pintype "passive"))
    )
    (net (code "161") (name "Net-(SW12-PadDO)") (class "Default")
      (node (ref "SW12") (pin "DO") (pinfunction "DO_DO") (pintype "passive"))
      (node (ref "SW13") (pin "DI") (pinfunction "DI_DI") (pintype "passive"))
    )
    (net (code "162") (name "Net-(SW13-PadDO)") (class "Default")
      (node (ref "SW13") (pin "DO") (pinfunction "DO_DO") (pintype "passive"))
      (node (ref "SW15") (pin "DI") (pinfunction "DI_DI") (pintype "passive"))
    )
    (net (code "163") (name "Net-(SW14-PadDI)") (class "Default")
      (node (ref "SW14") (pin "DI") (pinfunction "DI_DI") (pintype "passive"))
      (node (ref "SW15") (pin "DO") (pinfunction "DO_DO") (pintype "passive"))
    )
    (net (code "164") (name "Net-(SW14-PadDO)") (class "Default")
      (node (ref "SW14") (pin "DO") (pinfunction "DO_DO") (pintype "passive"))
      (node (ref "SW17") (pin "DI") (pinfunction "DI_DI") (pintype "passive"))
    )
    (net (code "165") (name "Net-(SW16-PadDI)") (class "Default")
      (node (ref "SW16") (pin "DI") (pinfunction "DI_DI") (pintype "passive"))
      (node (ref "SW17") (pin "DO") (pinfunction "DO_DO") (pintype "passive"))
    )
    (net (code "166") (name "Net-(SW18-PadDI)") (class "Default")
      (node (ref "SW18") (pin "DI") (pinfunction "DI_DI") (pintype "passive"))
      (node (ref "SW21") (pin "DO") (pinfunction "DO_DO") (pintype "passive"))
    )
    (net (code "167") (name "Net-(SW18-PadDO)") (class "Default")
      (node (ref "SW18") (pin "DO") (pinfunction "DO_DO") (pintype "passive"))
      (node (ref "SW19") (pin "DI") (pinfunction "DI_DI") (pintype "passive"))
    )
    (net (code "168") (name "Net-(SW20-PadDI)") (class "Default")
      (node (ref "SW20") (pin "DI") (pinfunction "DI_DI") (pintype "passive"))
      (node (ref "SW22") (pin "DO") (pinfunction "DO_DO") (pintype "passive"))
    )
    (net (code "169") (name "Net-(SW20-PadDO)") (class "Default")
      (node (ref "SW20") (pin "DO") (pinfunction "DO_DO") (pintype "passive"))
      (node (ref "SW21") (pin "DI") (pinfunction "DI_DI") (pintype "passive"))
    )
    (net (code "170") (name "Net-(SW22-PadDI)") (class "Default")
      (node (ref "SW22") (pin "DI") (pinfunction "DI_DI") (pintype "passive"))
      (node (ref "SW23") (pin "DO") (pinfunction "DO_DO") (pintype "passive"))
    )
    (net (code "171") (name "Net-(SW23-PadDI)") (class "Default")
      (node (ref "SW23") (pin "DI") (pinfunction "DI_DI") (pintype "passive"))
      (node (ref "SW7") (pin "DO") (pinfunction "DO_DO") (pintype "passive"))
    )
    (net (code "172") (name "Net-(SW24-PadDO)") (class "Default")
      (node (ref "SW24") (pin "DO") (pinfunction "DO_DO") (pintype "passive"))
      (node (ref "SW26") (pin "DI") (pinfunction "DI_DI") (pintype "passive"))
    )
    (net (code "173") (name "Net-(SW25-PadDI)") (class "Default")
      (node (ref "SW25") (pin "DI") (pinfunction "DI_DI") (pintype "passive"))
      (node (ref "SW26") (pin "DO") (pinfunction "DO_DO") (pintype "passive"))
    )
    (net (code "174") (name "Net-(SW25-PadDO)") (class "Default")
      (node (ref "SW25") (pin "DO") (pinfunction "DO_DO") (pintype "passive"))
      (node (ref "SW28") (pin "DI") (pinfunction "DI_DI") (pintype "passive"))
    )
    (net (code "175") (name "Net-(SW28-PadDO)") (class "Default")
      (node (ref "SW28") (pin "DO") (pinfunction "DO_DO") (pintype "passive"))
      (node (ref "SW34") (pin "DI") (pinfunction "DI_DI") (pintype "passive"))
    )
    (net (code "176") (name "Net-(SW29-PadDI)") (class "Default")
      (node (ref "SW29") (pin "DI") (pinfunction "DI_DI") (pintype "passive"))
      (node (ref "SW32") (pin "DO") (pinfunction "DO_DO") (pintype "passive"))
    )
    (net (code "177") (name "Net-(SW29-PadDO)") (class "Default")
      (node (ref "SW29") (pin "DO") (pinfunction "DO_DO") (pintype "passive"))
      (node (ref "SW35") (pin "DI") (pinfunction "DI_DI") (pintype "passive"))
    )
    (net (code "178") (name "Net-(SW31-PadDI)") (class "Default")
      (node (ref "SW31") (pin "DI") (pinfunction "DI_DI") (pintype "passive"))
      (node (ref "SW33") (pin "DO") (pinfunction "DO_DO") (pintype "passive"))
    )
    (net (code "179") (name "Net-(SW31-PadDO)") (class "Default")
      (node (ref "SW31") (pin "DO") (pinfunction "DO_DO") (pintype "passive"))
      (node (ref "SW32") (pin "DI") (pinfunction "DI_DI") (pintype "passive"))
    )
    (net (code "180") (name "Net-(SW33-PadDI)") (class "Default")
      (node (ref "SW33") (pin "DI") (pinfunction "DI_DI") (pintype "passive"))
      (node (ref "SW34") (pin "DO") (pinfunction "DO_DO") (pintype "passive"))
    )
    (net (code "181") (name "Net-(SW35-PadDO)") (class "Default")
      (node (ref "SW35") (pin "DO") (pinfunction "DO_DO") (pintype "passive"))
      (node (ref "SW36") (pin "DI") (pinfunction "DI_DI") (pintype "passive"))
    )
    (net (code "182") (name "Net-(SW36-PadDO)") (class "Default")
      (node (ref "SW36") (pin "DO") (pinfunction "DO_DO") (pintype "passive"))
      (node (ref "SW38") (pin "DI") (pinfunction "DI_DI") (pintype "passive"))
    )
    (net (code "183") (name "Net-(SW37-PadDI)") (class "Default")
      (node (ref "SW37") (pin "DI") (pinfunction "DI_DI") (pintype "passive"))
      (node (ref "SW38") (pin "DO") (pinfunction "DO_DO") (pintype "passive"))
    )
    (net (code "184") (name "Net-(SW37-PadDO)") (class "Default")
      (node (ref "SW37") (pin "DO") (pinfunction "DO_DO") (pintype "passive"))
      (node (ref "SW40") (pin "DI") (pinfunction "DI_DI") (pintype "passive"))
    )
    (net (code "185") (name "Net-(SW40-PadDO)") (class "Default")
      (node (ref "SW40") (pin "DO") (pinfunction "DO_DO") (pintype "passive"))
      (node (ref "SW46") (pin "DI") (pinfunction "DI_DI") (pintype "passive"))
    )
    (net (code "186") (name "Net-(SW41-PadDI)") (class "Default")
      (node (ref "SW41") (pin "DI") (pinfunction "DI_DI") (pintype "passive"))
      (node (ref "SW44") (pin "DO") (pinfunction "DO_DO") (pintype "passive"))
    )
    (net (code "187") (name "Net-(SW41-PadDO)") (class "Default")
      (node (ref "SW41") (pin "DO") (pinfunction "DO_DO") (pintype "passive"))
      (node (ref "SW42") (pin "DI") (pinfunction "DI_DI") (pintype "passive"))
    )
    (net (code "188") (name "Net-(SW42-PadDO)") (class "Default")
      (node (ref "SW42") (pin "DO") (pinfunction "DO_DO") (pintype "passive"))
      (node (ref "SW47") (pin "DI") (pinfunction "DI_DI") (pintype "passive"))
    )
    (net (code "189") (name "Net-(SW43-PadDI)") (class "Default")
      (node (ref "SW43") (pin "DI") (pinfunction "DI_DI") (pintype "passive"))
      (node (ref "SW45") (pin "DO") (pinfunction "DO_DO") (pintype "passive"))
    )
    (net (code "190") (name "Net-(SW43-PadDO)") (class "Default")
      (node (ref "SW43") (pin "DO") (pinfunction "DO_DO") (pintype "passive"))
      (node (ref "SW44") (pin "DI") (pinfunction "DI_DI") (pintype "passive"))
    )
    (net (code "191") (name "Net-(SW45-PadDI)") (class "Default")
      (node (ref "SW45") (pin "DI") (pinfunction "DI_DI") (pintype "passive"))
      (node (ref "SW46") (pin "DO") (pinfunction "DO_DO") (pintype "passive"))
    )
    (net (code "192") (name "Net-(SW47-PadDO)") (class "Default")
      (node (ref "SW47") (pin "DO") (pinfunction "DO_DO") (pintype "passive"))
      (node (ref "SW48") (pin "DI") (pinfunction "DI_DI") (pintype "passive"))
    )
    (net (code "193") (name "Net-(SW48-PadDO)") (class "Default")
      (node (ref "SW48") (pin "DO") (pinfunction "DO_DO") (pintype "passive"))
      (node (ref "SW50") (pin "DI") (pinfunction "DI_DI") (pintype "passive"))
    )
    (net (code "194") (name "Net-(SW49-PadDI)") (class "Default")
      (node (ref "SW49") (pin "DI") (pinfunction "DI_DI") (pintype "passive"))
      (node (ref "SW50") (pin "DO") (pinfunction "DO_DO") (pintype "passive"))
    )
    (net (code "195") (name "Net-(SW49-PadDO)") (class "Default")
      (node (ref "SW49") (pin "DO") (pinfunction "DO_DO") (pintype "passive"))
      (node (ref "SW52") (pin "DI") (pinfunction "DI_DI") (pintype "passive"))
    )
    (net (code "196") (name "Net-(SW52-PadDO)") (class "Default")
      (node (ref "SW52") (pin "DO") (pinfunction "DO_DO") (pintype "passive"))
      (node (ref "SW58") (pin "DI") (pinfunction "DI_DI") (pintype "passive"))
    )
    (net (code "197") (name "Net-(SW53-PadDI)") (class "Default")
      (node (ref "SW53") (pin "DI") (pinfunction "DI_DI") (pintype "passive"))
      (node (ref "SW56") (pin "DO") (pinfunction "DO_DO") (pintype "passive"))
    )
    (net (code "198") (name "Net-(SW53-PadDO)") (class "Default")
      (node (ref "SW53") (pin "DO") (pinfunction "DO_DO") (pintype "passive"))
      (node (ref "SW59") (pin "DI") (pinfunction "DI_DI") (pintype "passive"))
    )
    (net (code "199") (name "Net-(SW55-PadDI)") (class "Default")
      (node (ref "SW55") (pin "DI") (pinfunction "DI_DI") (pintype "passive"))
      (node (ref "SW57") (pin "DO") (pinfunction "DO_DO") (pintype "passive"))
    )
    (net (code "200") (name "Net-(SW55-PadDO)") (class "Default")
      (node (ref "SW55") (pin "DO") (pinfunction "DO_DO") (pintype "passive"))
      (node (ref "SW56") (pin "DI") (pinfunction "DI_DI") (pintype "passive"))
    )
    (net (code "201") (name "Net-(SW57-PadDI)") (class "Default")
      (node (ref "SW57") (pin "DI") (pinfunction "DI_DI") (pintype "passive"))
      (node (ref "SW58") (pin "DO") (pinfunction "DO_DO") (pintype "passive"))
    )
    (net (code "202") (name "Net-(SW59-PadDO)") (class "Default")
      (node (ref "SW59") (pin "DO") (pinfunction "DO_DO") (pintype "passive"))
      (node (ref "SW60") (pin "DI") (pinfunction "DI_DI") (pintype "passive"))
    )
    (net (code "203") (name "Net-(SW60-PadDO)") (class "Default")
      (node (ref "SW60") (pin "DO") (pinfunction "DO_DO") (pintype "passive"))
      (node (ref "SW62") (pin "DI") (pinfunction "DI_DI") (pintype "passive"))
    )
    (net (code "204") (name "Net-(SW61-PadDI)") (class "Default")
      (node (ref "SW61") (pin "DI") (pinfunction "DI_DI") (pintype "passive"))
      (node (ref "SW62") (pin "DO") (pinfunction "DO_DO") (pintype "passive"))
    )
    (net (code "205") (name "Net-(SW61-PadDO)") (class "Default")
      (node (ref "SW61") (pin "DO") (pinfunction "DO_DO") (pintype "passive"))
      (node (ref "SW64") (pin "DI") (pinfunction "DI_DI") (pintype "passive"))
    )
    (net (code "206") (name "Net-(SW64-PadDO)") (class "Default")
      (node (ref "SW64") (pin "DO") (pinfunction "DO_DO") (pintype "passive"))
      (node (ref "SW70") (pin "DI") (pinfunction "DI_DI") (pintype "passive"))
    )
    (net (code "207") (name "Net-(SW65-PadDI)") (class "Default")
      (node (ref "SW65") (pin "DI") (pinfunction "DI_DI") (pintype "passive"))
      (node (ref "SW68") (pin "DO") (pinfunction "DO_DO") (pintype "passive"))
    )
    (net (code "208") (name "Net-(SW65-PadDO)") (class "Default")
      (node (ref "SW65") (pin "DO") (pinfunction "DO_DO") (pintype "passive"))
      (node (ref "SW66") (pin "DI") (pinfunction "DI_DI") (pintype "passive"))
    )
    (net (code "209") (name "Net-(SW66-PadDO)") (class "Default")
      (node (ref "SW66") (pin "DO") (pinfunction "DO_DO") (pintype "passive"))
      (node (ref "SW71") (pin "DI") (pinfunction "DI_DI") (pintype "passive"))
    )
    (net (code "210") (name "Net-(SW67-PadDI)") (class "Default")
      (node (ref "SW67") (pin "DI") (pinfunction "DI_DI") (pintype "passive"))
      (node (ref "SW69") (pin "DO") (pinfunction "DO_DO") (pintype "passive"))
    )
    (net (code "211") (name "Net-(SW67-PadDO)") (class "Default")
      (node (ref "SW67") (pin "DO") (pinfunction "DO_DO") (pintype "passive"))
      (node (ref "SW68") (pin "DI") (pinfunction "DI_DI") (pintype "passive"))
    )
    (net (code "212") (name "Net-(SW69-PadDI)") (class "Default")
      (node (ref "SW69") (pin "DI") (pinfunction "DI_DI") (pintype "passive"))
      (node (ref "SW70") (pin "DO") (pinfunction "DO_DO") (pintype "passive"))
    )
    (net (code "213") (name "Net-(SW71-PadDO)") (class "Default")
      (node (ref "SW71") (pin "DO") (pinfunction "DO_DO") (pintype "passive"))
      (node (ref "SW72") (pin "DI") (pinfunction "DI_DI") (pintype "passive"))
    )
    (net (code "214") (name "Net-(SW72-PadDO)") (class "Default")
      (node (ref "SW72") (pin "DO") (pinfunction "DO_DO") (pintype "passive"))
      (node (ref "SW74") (pin "DI") (pinfunction "DI_DI") (pintype "passive"))
    )
    (net (code "215") (name "Net-(SW73-PadDI)") (class "Default")
      (node (ref "SW73") (pin "DI") (pinfunction "DI_DI") (pintype "passive"))
      (node (ref "SW74") (pin "DO") (pinfunction "DO_DO") (pintype "passive"))
    )
    (net (code "216") (name "Net-(SW73-PadDO)") (class "Default")
      (node (ref "SW73") (pin "DO") (pinfunction "DO_DO") (pintype "passive"))
      (node (ref "SW76") (pin "DI") (pinfunction "DI_DI") (pintype "passive"))
    )
    (net (code "217") (name "Net-(SW75-PadDI)") (class "Default")
      (node (ref "SW75") (pin "DI") (pinfunction "DI_DI") (pintype "passive"))
      (node (ref "SW76") (pin "DO") (pinfunction "DO_DO") (pintype "passive"))
    )
    (net (code "218") (name "Net-(SW75-PadDO)") (class "Default")
      (node (ref "SW75") (pin "DO") (pinfunction "DO_DO") (pintype "passive"))
      (node (ref "SW82") (pin "DI") (pinfunction "DI_DI") (pintype "passive"))
    )
    (net (code "219") (name "Net-(SW78-PadDI)") (class "Default")
      (node (ref "SW78") (pin "DI") (pinfunction "DI_DI") (pintype "passive"))
      (node (ref "SW80") (pin "DO") (pinfunction "DO_DO") (pintype "passive"))
    )
    (net (code "220") (name "Net-(SW78-PadDO)") (class "Default")
      (node (ref "SW78") (pin "DO") (pinfunction "DO_DO") (pintype "passive"))
      (node (ref "SW83") (pin "DI") (pinfunction "DI_DI") (pintype "passive"))
    )
    (net (code "221") (name "Net-(SW80-PadDI)") (class "Default")
      (node (ref "SW80") (pin "DI") (pinfunction "DI_DI") (pintype "passive"))
      (node (ref "SW81") (pin "DO") (pinfunction "DO_DO") (pintype "passive"))
    )
    (net (code "222") (name "Net-(SW81-PadDI)") (class "Default")
      (node (ref "SW81") (pin "DI") (pinfunction "DI_DI") (pintype "passive"))
      (node (ref "SW82") (pin "DO") (pinfunction "DO_DO") (pintype "passive"))
    )
    (net (code "223") (name "Net-(SW83-PadDO)") (class "Default")
      (node (ref "SW83") (pin "DO") (pinfunction "DO_DO") (pintype "passive"))
      (node (ref "SW84") (pin "DI") (pinfunction "DI_DI") (pintype "passive"))
    )
    (net (code "224") (name "Net-(SW84-PadDO)") (class "Default")
      (node (ref "SW84") (pin "DO") (pinfunction "DO_DO") (pintype "passive"))
      (node (ref "SW86") (pin "DI") (pinfunction "DI_DI") (pintype "passive"))
    )
    (net (code "225") (name "Net-(SW85-PadDI)") (class "Default")
      (node (ref "SW85") (pin "DI") (pinfunction "DI_DI") (pintype "passive"))
      (node (ref "SW86") (pin "DO") (pinfunction "DO_DO") (pintype "passive"))
    )
    (net (code "226") (name "Net-(SW85-PadDO)") (class "Default")
      (node (ref "SW85") (pin "DO") (pinfunction "DO_DO") (pintype "passive"))
      (node (ref "SW88") (pin "DI") (pinfunction "DI_DI") (pintype "passive"))
    )
    (net (code "227") (name "Net-(SW87-PadDI)") (class "Default")
      (node (ref "SW87") (pin "DI") (pinfunction "DI_DI") (pintype "passive"))
      (node (ref "SW88") (pin "DO") (pinfunction "DO_DO") (pintype "passive"))
    )
    (net (code "228") (name "Net-(SW87-PadDO)") (class "Default")
      (node (ref "SW87") (pin "DO") (pinfunction "DO_DO") (pintype "passive"))
      (node (ref "SW94") (pin "DI") (pinfunction "DI_DI") (pintype "passive"))
    )
    (net (code "229") (name "Net-(SW89-PadDI)") (class "Default")
      (node (ref "SW89") (pin "DI") (pinfunction "DI_DI") (pintype "passive"))
      (node (ref "SW92") (pin "DO") (pinfunction "DO_DO") (pintype "passive"))
    )
    (net (code "230") (name "Net-(SW89-PadDO)") (class "Default")
      (node (ref "SW89") (pin "DO") (pinfunction "DO_DO") (pintype "passive"))
      (node (ref "SW95") (pin "DI") (pinfunction "DI_DI") (pintype "passive"))
    )
    (net (code "231") (name "Net-(SW91-PadDI)") (class "Default")
      (node (ref "SW91") (pin "DI") (pinfunction "DI_DI") (pintype "passive"))
      (node (ref "SW93") (pin "DO") (pinfunction "DO_DO") (pintype "passive"))
    )
    (net (code "232") (name "Net-(SW91-PadDO)") (class "Default")
      (node (ref "SW91") (pin "DO") (pinfunction "DO_DO") (pintype "passive"))
      (node (ref "SW92") (pin "DI") (pinfunction "DI_DI") (pintype "passive"))
    )
    (net (code "233") (name "Net-(SW93-PadDI)") (class "Default")
      (node (ref "SW93") (pin "DI") (pinfunction "DI_DI") (pintype "passive"))
      (node (ref "SW94") (pin "DO") (pinfunction "DO_DO") (pintype "passive"))
    )
    (net (code "234") (name "Net-(SW95-PadDO)") (class "Default")
      (node (ref "SW95") (pin "DO") (pinfunction "DO_DO") (pintype "passive"))
      (node (ref "SW96") (pin "DI") (pinfunction "DI_DI") (pintype "passive"))
    )
    (net (code "235") (name "Net-(SW96-PadDO)") (class "Default")
      (node (ref "SW96") (pin "DO") (pinfunction "DO_DO") (pintype "passive"))
      (node (ref "SW98") (pin "DI") (pinfunction "DI_DI") (pintype "passive"))
    )
    (net (code "236") (name "Net-(SW97-PadDI)") (class "Default")
      (node (ref "SW97") (pin "DI") (pinfunction "DI_DI") (pintype "passive"))
      (node (ref "SW98") (pin "DO") (pinfunction "DO_DO") (pintype "passive"))
    )
    (net (code "237") (name "Net-(SW100-PadDI)") (class "Default")
      (node (ref "SW100") (pin "DI") (pinfunction "DI_DI") (pintype "passive"))
      (node (ref "SW97") (pin "DO") (pinfunction "DO_DO") (pintype "passive"))
    )
    (net (code "238") (name "Net-(SW100-PadDO)") (class "Default")
      (node (ref "SW100") (pin "DO") (pinfunction "DO_DO") (pintype "passive"))
      (node (ref "SW99") (pin "DI") (pinfunction "DI_DI") (pintype "passive"))
    )
    (net (code "239") (name "Net-(SW101-PadDI)") (class "Default")
      (node (ref "SW101") (pin "DI") (pinfunction "DI_DI") (pintype "passive"))
      (node (ref "SW104") (pin "DO") (pinfunction "DO_DO") (pintype "passive"))
    )
    (net (code "240") (name "Net-(SW101-PadDO)") (class "Default")
      (node (ref "SW101") (pin "DO") (pinfunction "DO_DO") (pintype "passive"))
      (node (ref "SW102") (pin "DI") (pinfunction "DI_DI") (pintype "passive"))
    )
    (net (code "241") (name "Net-(SW104-PadDI)") (class "Default")
      (node (ref "SW104") (pin "DI") (pinfunction "DI_DI") (pintype "passive"))
      (node (ref "SW99") (pin "DO") (pinfunction "DO_DO") (pintype "passive"))
    )
    (net (code "242") (name "Net-(U3-P0.28)") (class "Default")
      (node (ref "H3") (pin "3") (pinfunction "3_3") (pintype "passive"))
      (node (ref "U3") (pin "3") (pinfunction "P0.28_3") (pintype "passive"))
    )
    (net (code "243") (name "Net-(U3-P0.29)") (class "Default")
      (node (ref "H3") (pin "4") (pinfunction "4_4") (pintype "passive"))
      (node (ref "U3") (pin "4") (pinfunction "P0.29_4") (pintype "passive"))
    )
    (net (code "244") (name "Net-(U3-P1.11)") (class "Default")
      (node (ref "H3") (pin "7") (pinfunction "7_7") (pintype "passive"))
      (node (ref "U3") (pin "7") (pinfunction "P1.11_7") (pintype "passive"))
    )
    (net (code "245") (name "Net-(U3-P1.12)") (class "Default")
      (node (ref "H1") (pin "1") (pinfunction "1_1") (pintype "passive"))
      (node (ref "U3") (pin "8") (pinfunction "P1.12_8") (pintype "passive"))
    )
    (net (code "246") (name "Net-(U3-P1.13)") (class "Default")
      (node (ref "H1") (pin "2") (pinfunction "2_2") (pintype "passive"))
      (node (ref "U3") (pin "9") (pinfunction "P1.13_9") (pintype "passive"))
    )
    (net (code "247") (name "Net-(U3-P1.14)") (class "Default")
      (node (ref "H1") (pin "3") (pinfunction "3_3") (pintype "passive"))
      (node (ref "U3") (pin "10") (pinfunction "P1.14_10") (pintype "passive"))
    )
    (net (code "248") (name "Net-(U3-P1.15)") (class "Default")
      (node (ref "H1") (pin "4") (pinfunction "4_4") (pintype "passive"))
      (node (ref "U3") (pin "11") (pinfunction "P1.15_11") (pintype "passive"))
    )
    (net (code "249") (name "unconnected-(U3-BAT-Pad21)") (class "Default")
      (node (ref "U3") (pin "21") (pinfunction "BAT_21") (pintype "passive"))
    )
    (net (code "250") (name "unconnected-(U3-RST-Pad23)") (class "Default")
      (node (ref "U3") (pin "23") (pinfunction "RST_23") (pintype "passive"))
    )
  )
)
